# -002_plata_rele.net
KiCad netlist of a schematic drawn in Altium Designer
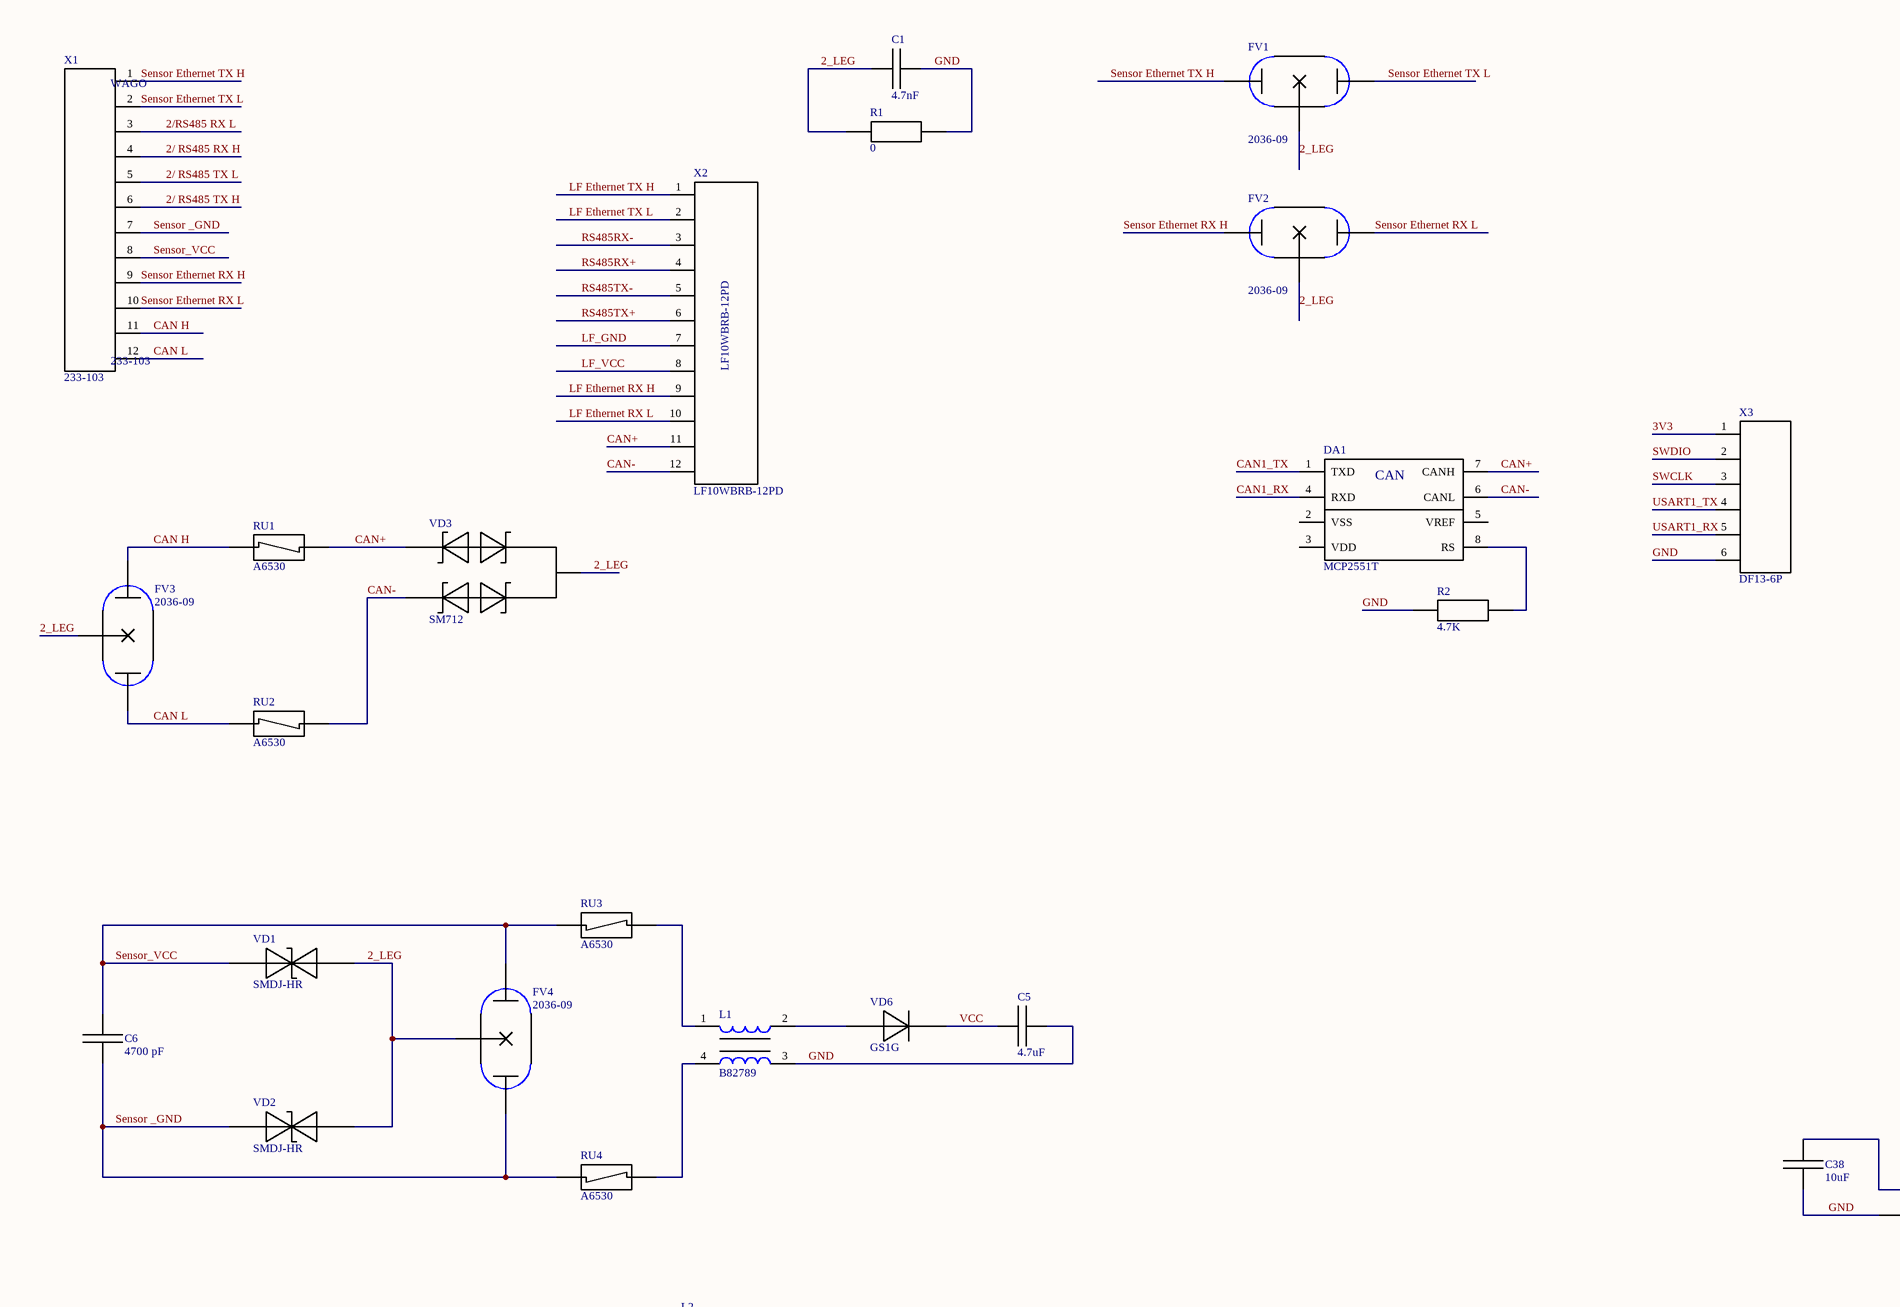
[diagram p0: КБ-002_plata_rele.SchDoc, top left]
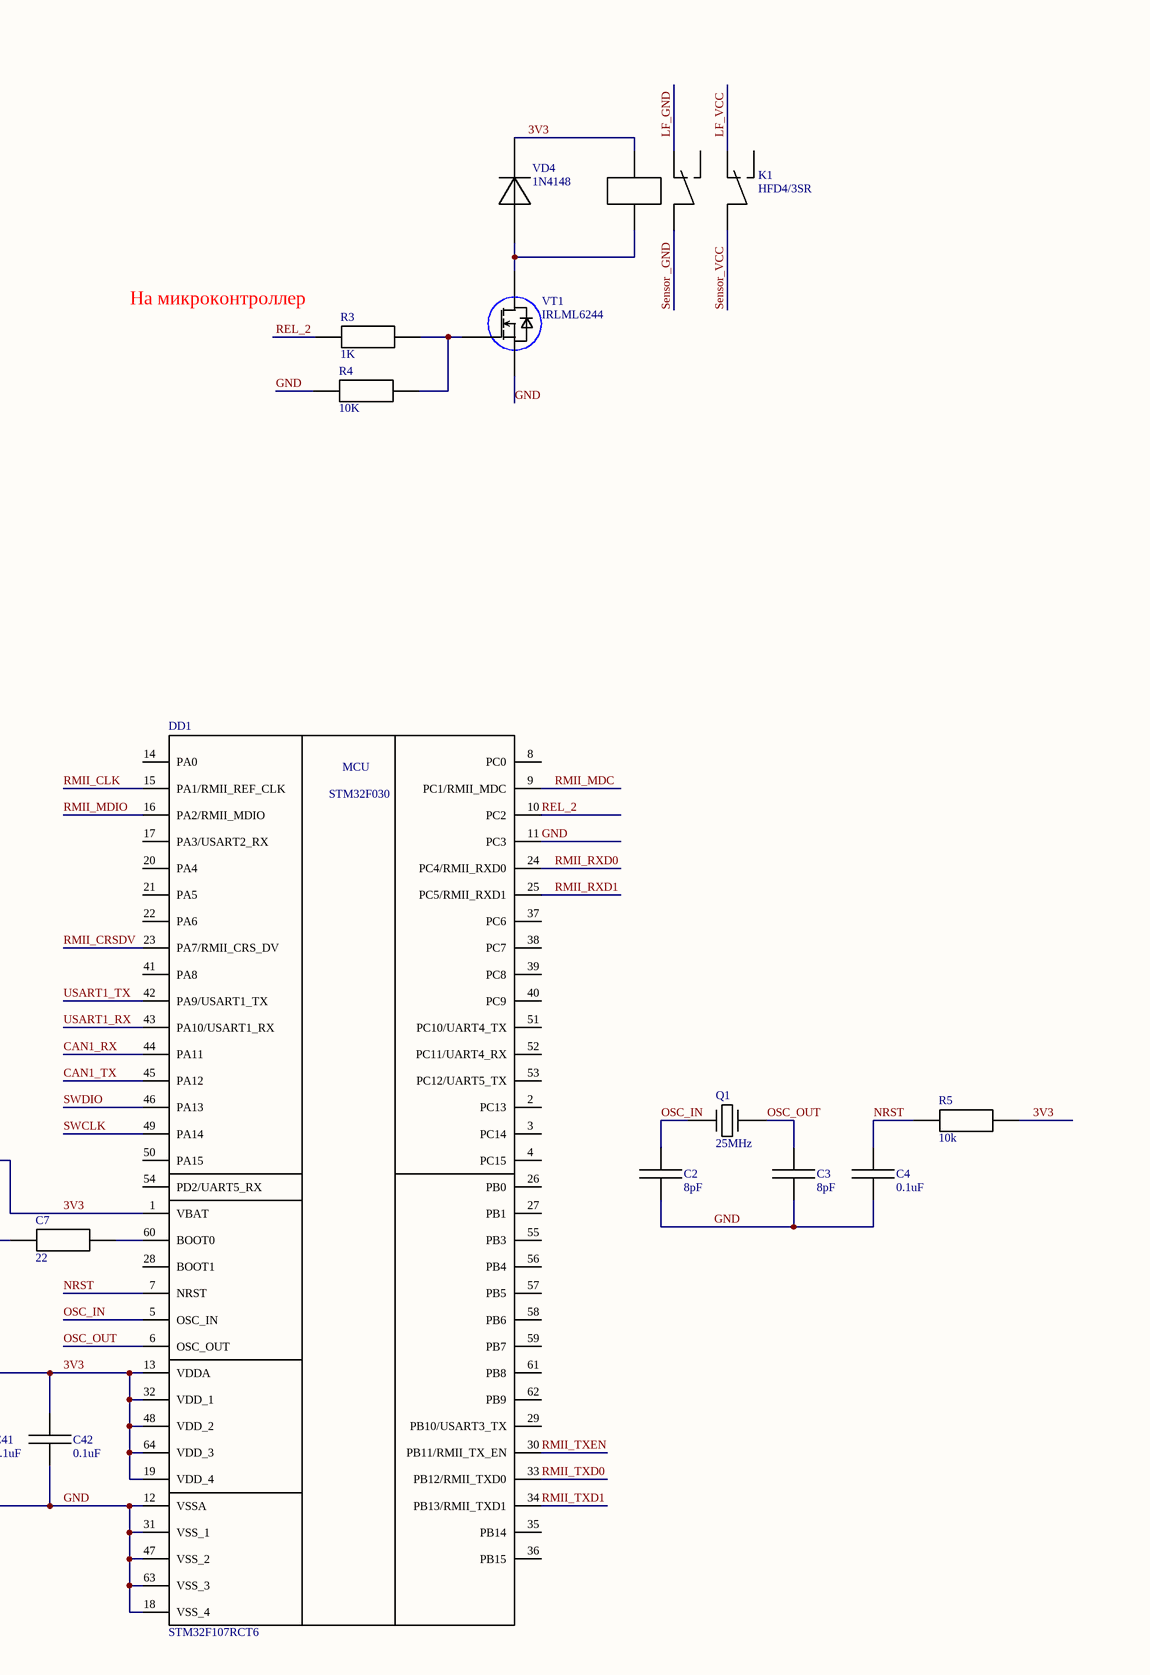
[diagram p1: КБ-002_plata_rele.SchDoc, top right]
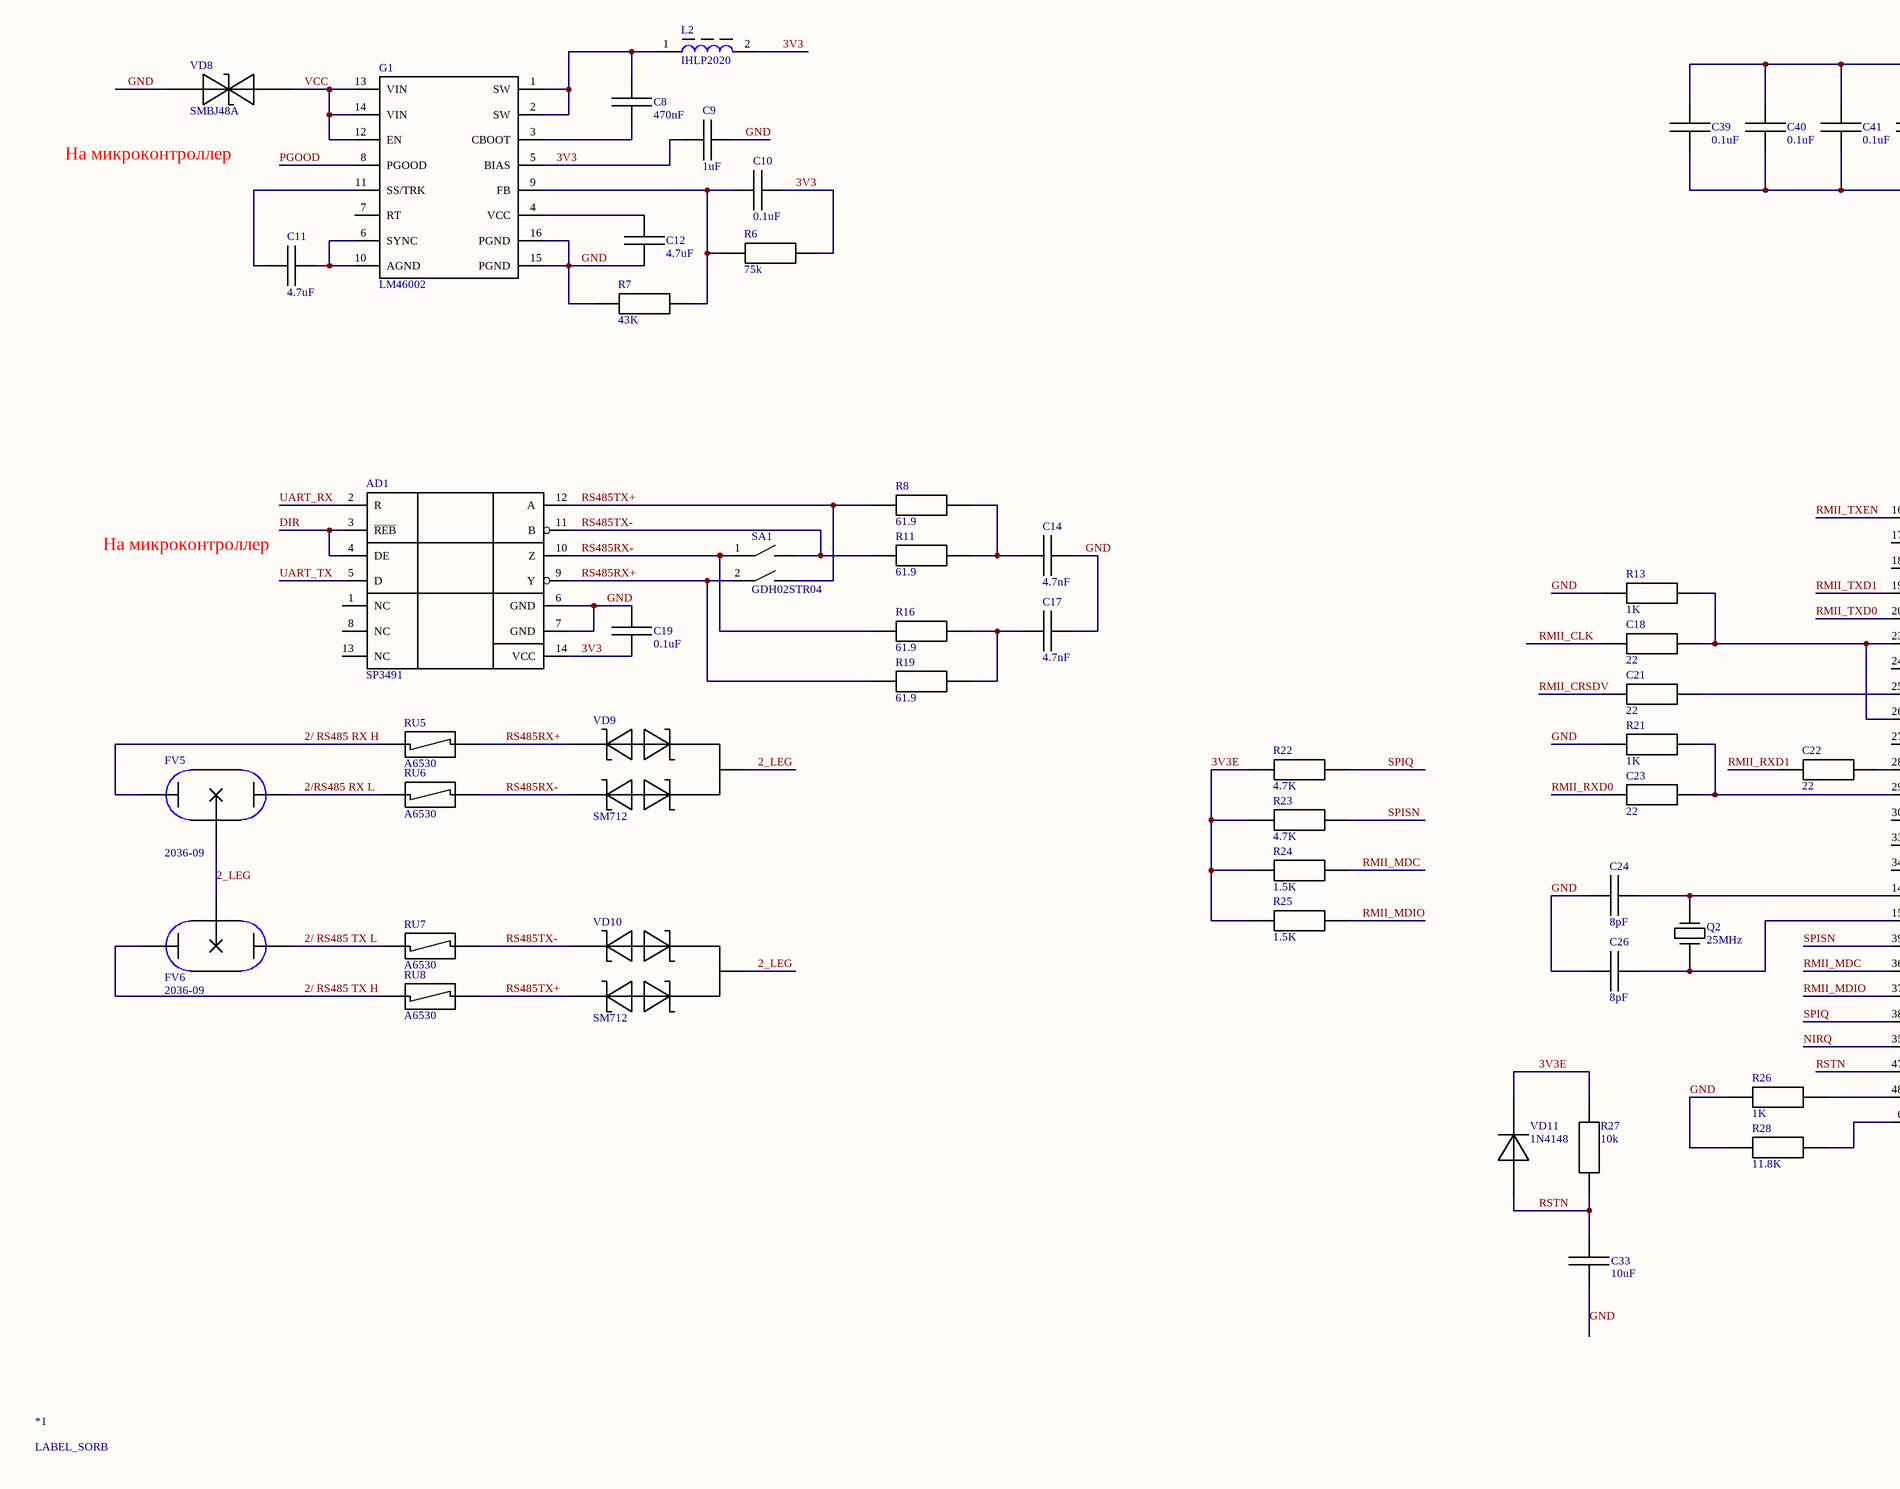
[diagram p2: КБ-002_plata_rele.SchDoc, bottom left]
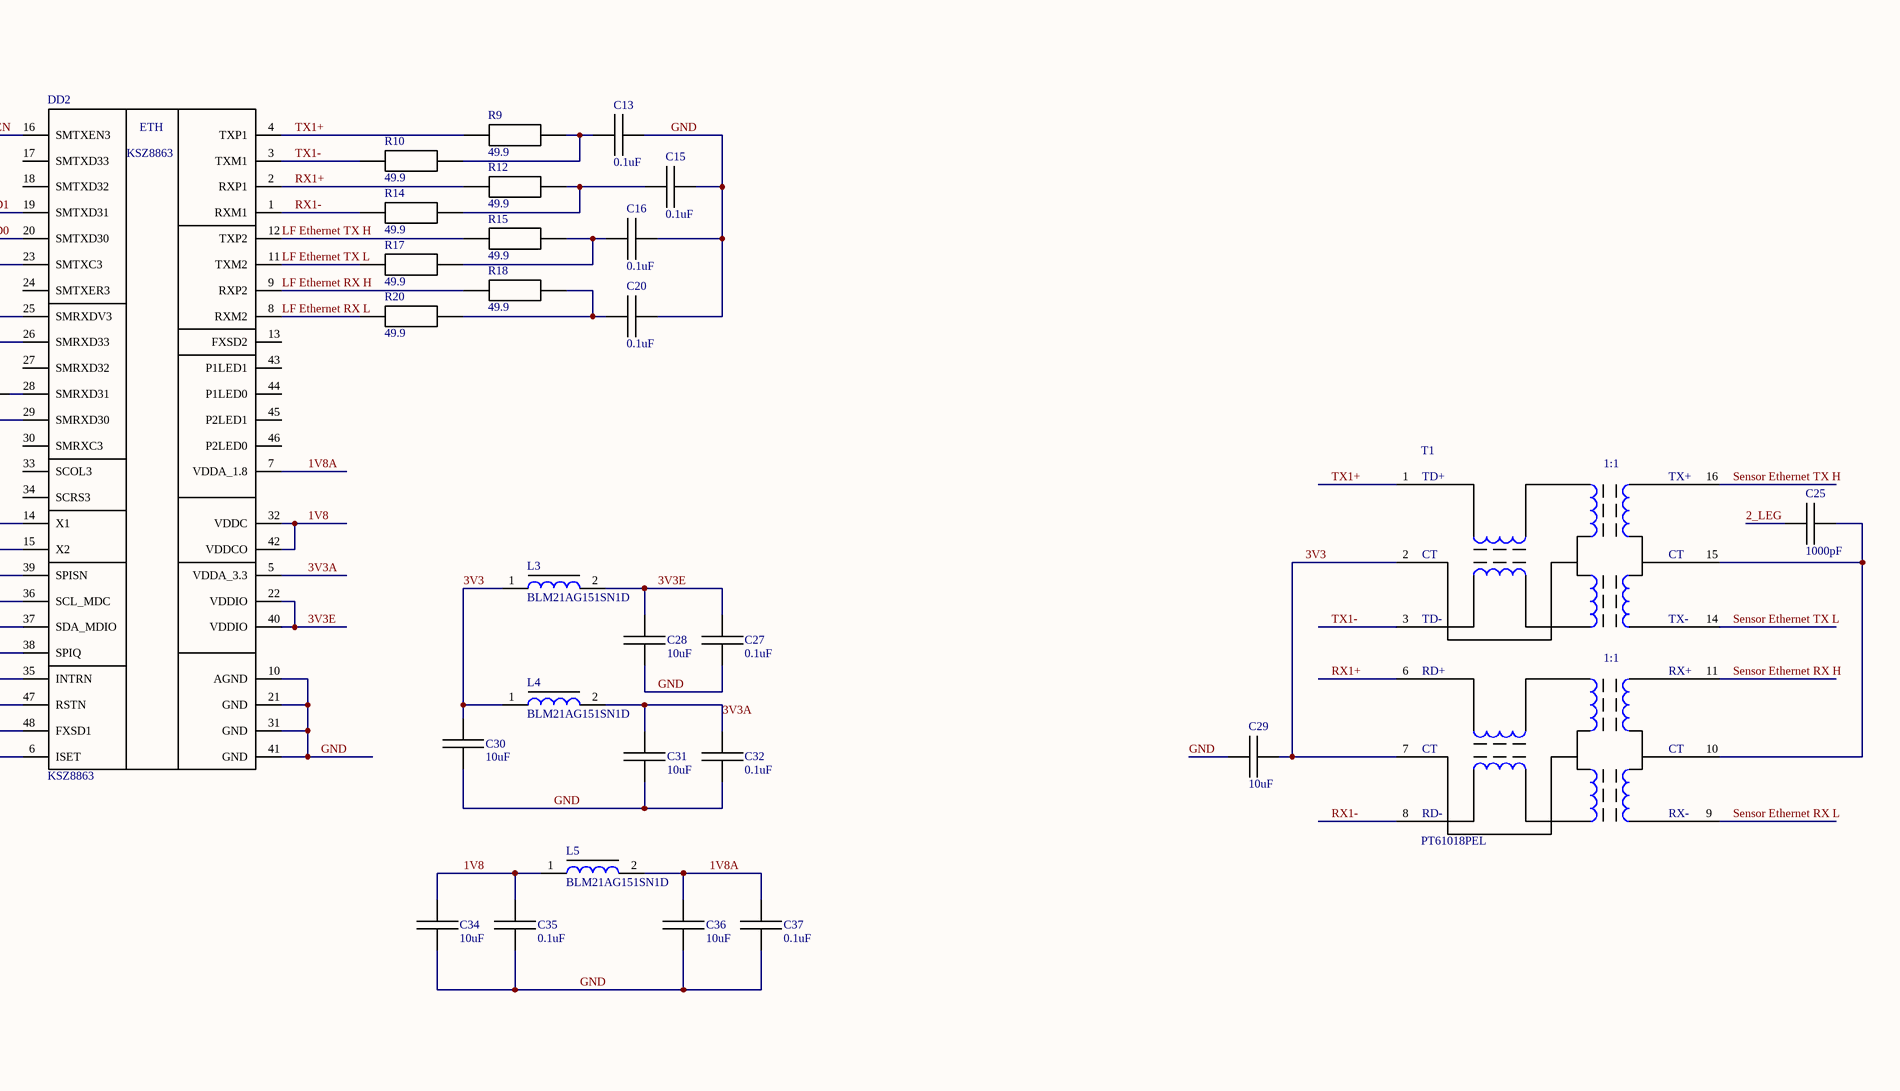
[diagram p3: КБ-002_plata_rele.SchDoc, bottom right]

(export (version "E")
  (design (tool "Eeschema 10.0.6"))
  (components
    (comp (ref "*1")
      (value "LABEL_SORB")
      (footprint "SorbGroup")
      (libsource (lib "pozarka") (part "LABEL_SORB"))
    )
    (comp (ref "AD1")
      (value "SP3491")
      (footprint "SOIC-14")
      (description "SP3491CN-L, Приемопередатчик RS485, 3В-3.465В, NSOIC-14")
      (libsource (lib "pozarka") (part "SP3491"))
    )
    (comp (ref "C1")
      (value "4.7nF")
      (footprint "CAP0402")
      (description "Кер.чип.конд. 0402 X5R 4.7нФ 16В 10%, GRM155R61C472KA01D")
      (libsource (lib "pozarka") (part "CAP0402 4.7nF"))
    )
    (comp (ref "C2")
      (value "8pF")
      (footprint "CAP0402")
      (description "Кер.чип.конд. 0402 C0G 8пФ 50В, GRM1555C1H8R0CA01D")
      (libsource (lib "pozarka") (part "CAP0402 8pF"))
    )
    (comp (ref "C3")
      (value "8pF")
      (footprint "CAP0402")
      (description "Кер.чип.конд. 0402 C0G 8пФ 50В, GRM1555C1H8R0CA01D")
      (libsource (lib "pozarka") (part "CAP0402 8pF"))
    )
    (comp (ref "C4")
      (value "0.1uF")
      (footprint "CAP0402")
      (description "Кер.ЧИП конд. 0.1мкФ X7R 10%, 0402, 16В, GRM155R71C104K")
      (libsource (lib "pozarka") (part "CAP0402 0.1uF"))
    )
    (comp (ref "C5")
      (value "4.7uF")
      (footprint "CAP0402")
      (description "Кер.чип.конд. 0402 X5R 4.7мкФ 4В 20%, GRM155R60G475ME87D")
      (libsource (lib "pozarka") (part "CAP0402 4,7uF"))
    )
    (comp (ref "C6")
      (value "4700 pF")
      (footprint "CAP1812")
      (description "4700пф X7R 2000в 10% (1812) Чип керам,конденсатор MA1812XR472K202ERG (FV43X472K202EFG")
      (libsource (lib "pozarka") (part "CAP1812 4700pF"))
    )
    (comp (ref "C7")
      (value "22")
      (footprint "RES0402")
      (description "0.062Вт 0402 22 Ом, 1%, Чип резистор (SMD)")
      (libsource (lib "pozarka") (part "RES0402 22"))
    )
    (comp (ref "C8")
      (value "470nF")
      (footprint "CAP0402")
      (description "Кер.чип.конд. 0402 X5R 470нФ 10В 10% , GRM155R61A474KE15D")
      (libsource (lib "pozarka") (part "CAP0402 470nF"))
    )
    (comp (ref "C9")
      (value "1uF")
      (footprint "CAP0402")
      (description "Кер.ЧИП конд. 1мкФ X5R 10%, 0402, 10В, GRM155R61A105K")
      (libsource (lib "pozarka") (part "CAP0402 1uF"))
    )
    (comp (ref "C10")
      (value "0.1uF")
      (footprint "CAP0402")
      (description "Кер.ЧИП конд. 0.1мкФ X7R 10%, 0402, 16В, GRM155R71C104K")
      (libsource (lib "pozarka") (part "CAP0402 0.1uF"))
    )
    (comp (ref "C11")
      (value "4.7uF")
      (footprint "CAP0402")
      (description "Кер.чип.конд. 0402 X5R 4.7мкФ 4В 20%, GRM155R60G475ME87D")
      (libsource (lib "pozarka") (part "CAP0402 4,7uF"))
    )
    (comp (ref "C12")
      (value "4.7uF")
      (footprint "CAP0402")
      (description "Кер.чип.конд. 0402 X5R 4.7мкФ 4В 20%, GRM155R60G475ME87D")
      (libsource (lib "pozarka") (part "CAP0402 4,7uF"))
    )
    (comp (ref "C13")
      (value "0.1uF")
      (footprint "CAP0402")
      (description "Кер.ЧИП конд. 0.1мкФ X7R 10%, 0402, 16В, GRM155R71C104K")
      (libsource (lib "pozarka") (part "CAP0402 0.1uF"))
    )
    (comp (ref "C14")
      (value "4.7nF")
      (footprint "CAP0402")
      (description "Кер.чип.конд. 0402 X5R 4.7нФ 16В 10%, GRM155R61C472KA01D")
      (libsource (lib "pozarka") (part "CAP0402 4.7nF"))
    )
    (comp (ref "C15")
      (value "0.1uF")
      (footprint "CAP0402")
      (description "Кер.ЧИП конд. 0.1мкФ X7R 10%, 0402, 16В, GRM155R71C104K")
      (libsource (lib "pozarka") (part "CAP0402 0.1uF"))
    )
    (comp (ref "C16")
      (value "0.1uF")
      (footprint "CAP0402")
      (description "Кер.ЧИП конд. 0.1мкФ X7R 10%, 0402, 16В, GRM155R71C104K")
      (libsource (lib "pozarka") (part "CAP0402 0.1uF"))
    )
    (comp (ref "C17")
      (value "4.7nF")
      (footprint "CAP0402")
      (description "Кер.чип.конд. 0402 X5R 4.7нФ 16В 10%, GRM155R61C472KA01D")
      (libsource (lib "pozarka") (part "CAP0402 4.7nF"))
    )
    (comp (ref "C18")
      (value "22")
      (footprint "RES0402")
      (description "0.062Вт 0402 22 Ом, 1%, Чип резистор (SMD)")
      (libsource (lib "pozarka") (part "RES0402 22"))
    )
    (comp (ref "C19")
      (value "0.1uF")
      (footprint "CAP0402")
      (description "Кер.ЧИП конд. 0.1мкФ X7R 10%, 0402, 16В, GRM155R71C104K")
      (libsource (lib "pozarka") (part "CAP0402 0.1uF"))
    )
    (comp (ref "C20")
      (value "0.1uF")
      (footprint "CAP0402")
      (description "Кер.ЧИП конд. 0.1мкФ X7R 10%, 0402, 16В, GRM155R71C104K")
      (libsource (lib "pozarka") (part "CAP0402 0.1uF"))
    )
    (comp (ref "C21")
      (value "22")
      (footprint "RES0402")
      (description "0.062Вт 0402 22 Ом, 1%, Чип резистор (SMD)")
      (libsource (lib "pozarka") (part "RES0402 22"))
    )
    (comp (ref "C22")
      (value "22")
      (footprint "RES0402")
      (description "0.062Вт 0402 22 Ом, 1%, Чип резистор (SMD)")
      (libsource (lib "pozarka") (part "RES0402 22"))
    )
    (comp (ref "C23")
      (value "22")
      (footprint "RES0402")
      (description "0.062Вт 0402 22 Ом, 1%, Чип резистор (SMD)")
      (libsource (lib "pozarka") (part "RES0402 22"))
    )
    (comp (ref "C24")
      (value "8pF")
      (footprint "CAP0402")
      (description "Кер.чип.конд. 0402 C0G 8пФ 50В, GRM1555C1H8R0CA01D")
      (libsource (lib "pozarka") (part "CAP0402 8pF"))
    )
    (comp (ref "C25")
      (value "1000pF")
      (footprint "CAP0402")
      (description "Кер.ЧИП конд. 1000пФ NP0 5%, 0402, 50В, GRM1555C1H102J")
      (libsource (lib "pozarka") (part "CAP0402 1000pF"))
    )
    (comp (ref "C26")
      (value "8pF")
      (footprint "CAP0402")
      (description "Кер.чип.конд. 0402 C0G 8пФ 50В, GRM1555C1H8R0CA01D")
      (libsource (lib "pozarka") (part "CAP0402 8pF"))
    )
    (comp (ref "C27")
      (value "0.1uF")
      (footprint "CAP0402")
      (description "Кер.ЧИП конд. 0.1мкФ X7R 10%, 0402, 16В, GRM155R71C104K")
      (libsource (lib "pozarka") (part "CAP0402 0.1uF"))
    )
    (comp (ref "C28")
      (value "10uF")
      (footprint "CAP0402")
      (description "Кер.чип.конд. 0402 X5R 10мкФ 2.5В 20%, GRM155R60E106ME16D")
      (libsource (lib "pozarka") (part "CAP0402 10uF"))
    )
    (comp (ref "C29")
      (value "10uF")
      (footprint "CAP0402")
      (description "Кер.чип.конд. 0402 X5R 10мкФ 2.5В 20%, GRM155R60E106ME16D")
      (libsource (lib "pozarka") (part "CAP0402 10uF"))
    )
    (comp (ref "C30")
      (value "10uF")
      (footprint "CAP0402")
      (description "Кер.чип.конд. 0402 X5R 10мкФ 2.5В 20%, GRM155R60E106ME16D")
      (libsource (lib "pozarka") (part "CAP0402 10uF"))
    )
    (comp (ref "C31")
      (value "10uF")
      (footprint "CAP0402")
      (description "Кер.чип.конд. 0402 X5R 10мкФ 2.5В 20%, GRM155R60E106ME16D")
      (libsource (lib "pozarka") (part "CAP0402 10uF"))
    )
    (comp (ref "C32")
      (value "0.1uF")
      (footprint "CAP0402")
      (description "Кер.ЧИП конд. 0.1мкФ X7R 10%, 0402, 16В, GRM155R71C104K")
      (libsource (lib "pozarka") (part "CAP0402 0.1uF"))
    )
    (comp (ref "C33")
      (value "10uF")
      (footprint "CAP0402")
      (description "Кер.чип.конд. 0402 X5R 10мкФ 2.5В 20%, GRM155R60E106ME16D")
      (libsource (lib "pozarka") (part "CAP0402 10uF"))
    )
    (comp (ref "C34")
      (value "10uF")
      (footprint "CAP0402")
      (description "Кер.чип.конд. 0402 X5R 10мкФ 2.5В 20%, GRM155R60E106ME16D")
      (libsource (lib "pozarka") (part "CAP0402 10uF"))
    )
    (comp (ref "C35")
      (value "0.1uF")
      (footprint "CAP0402")
      (description "Кер.ЧИП конд. 0.1мкФ X7R 10%, 0402, 16В, GRM155R71C104K")
      (libsource (lib "pozarka") (part "CAP0402 0.1uF"))
    )
    (comp (ref "C36")
      (value "10uF")
      (footprint "CAP0402")
      (description "Кер.чип.конд. 0402 X5R 10мкФ 2.5В 20%, GRM155R60E106ME16D")
      (libsource (lib "pozarka") (part "CAP0402 10uF"))
    )
    (comp (ref "C37")
      (value "0.1uF")
      (footprint "CAP0402")
      (description "Кер.ЧИП конд. 0.1мкФ X7R 10%, 0402, 16В, GRM155R71C104K")
      (libsource (lib "pozarka") (part "CAP0402 0.1uF"))
    )
    (comp (ref "C38")
      (value "10uF")
      (footprint "CAP0402")
      (description "Кер.чип.конд. 0402 X5R 10мкФ 2.5В 20%, GRM155R60E106ME16D")
      (libsource (lib "pozarka") (part "CAP0402 10uF"))
    )
    (comp (ref "C39")
      (value "0.1uF")
      (footprint "CAP0402")
      (description "Кер.ЧИП конд. 0.1мкФ X7R 10%, 0402, 16В, GRM155R71C104K")
      (libsource (lib "pozarka") (part "CAP0402 0.1uF"))
    )
    (comp (ref "C40")
      (value "0.1uF")
      (footprint "CAP0402")
      (description "Кер.ЧИП конд. 0.1мкФ X7R 10%, 0402, 16В, GRM155R71C104K")
      (libsource (lib "pozarka") (part "CAP0402 0.1uF"))
    )
    (comp (ref "C41")
      (value "0.1uF")
      (footprint "CAP0402")
      (description "Кер.ЧИП конд. 0.1мкФ X7R 10%, 0402, 16В, GRM155R71C104K")
      (libsource (lib "pozarka") (part "CAP0402 0.1uF"))
    )
    (comp (ref "C42")
      (value "0.1uF")
      (footprint "CAP0402")
      (description "Кер.ЧИП конд. 0.1мкФ X7R 10%, 0402, 16В, GRM155R71C104K")
      (libsource (lib "pozarka") (part "CAP0402 0.1uF"))
    )
    (comp (ref "DA1")
      (value "MCP2551T")
      (footprint "SO-8")
      (description "MCP2551T-I/SN, CAN приемопередатчик, быстрый [SO-8]")
      (libsource (lib "pozarka") (part "MCPT2551T"))
    )
    (comp (ref "DD1")
      (value "STM32F107RCT6")
      (footprint "TQFP64 10x10")
      (description "STM32F107RCT6, Микроконтроллер 32-Бит, Cortex-M3, 72МГц, 256КБ Flash [LQFP-64]")
      (libsource (lib "pozarka") (part "STM32F107"))
    )
    (comp (ref "DD2") (value "KSZ8863") (footprint "TQFP48-7x7") (libsource (lib "pozarka") (part "KSZ8863")))
    (comp (ref "FV1")
      (value "2036-09")
      (footprint "2036-09")
      (description "2036-09-SM-RPLF Газоразрядная трубка")
      (libsource (lib "pozarka") (part "2036-09"))
    )
    (comp (ref "FV2")
      (value "2036-09")
      (footprint "2036-09")
      (description "2036-09-SM-RPLF Газоразрядная трубка")
      (libsource (lib "pozarka") (part "2036-09"))
    )
    (comp (ref "FV3")
      (value "2036-09")
      (footprint "2036-09")
      (description "2036-09-SM-RPLF Газоразрядная трубка")
      (libsource (lib "pozarka") (part "2036-09"))
    )
    (comp (ref "FV4")
      (value "2036-09")
      (footprint "2036-09")
      (description "2036-09-SM-RPLF Газоразрядная трубка")
      (libsource (lib "pozarka") (part "2036-09"))
    )
    (comp (ref "FV5")
      (value "2036-09")
      (footprint "2036-09")
      (description "2036-09-SM-RPLF Газоразрядная трубка")
      (libsource (lib "pozarka") (part "2036-09"))
    )
    (comp (ref "FV6")
      (value "2036-09")
      (footprint "2036-09")
      (description "2036-09-SM-RPLF Газоразрядная трубка")
      (libsource (lib "pozarka") (part "2036-09"))
    )
    (comp (ref "G1") (value "LM46002") (footprint "HTSSOP-16") (libsource (lib "pozarka") (part "LM46002")))
    (comp (ref "K1")
      (value "HFD4/3SR")
      (footprint "HFD4/3")
      (description "HFD4/3SR (IM01GR), Реле 3VDC 2пер. 2A/250VAC")
      (libsource (lib "pozarka") (part "HFD4/3SR"))
    )
    (comp (ref "L1")
      (value "B82789")
      (footprint "SIMDAD 1812")
      (description "B82789C0104N002")
      (libsource (lib "pozarka") (part "B82789"))
    )
    (comp (ref "L2")
      (value "IHLP2020")
      (footprint "IHLP-2020CZ-51")
      (description "IHLP2020CZER100M11")
      (libsource (lib "pozarka") (part "IHLP2020CZER100M11"))
    )
    (comp (ref "L3")
      (value "BLM21AG151SN1D")
      (footprint "IND0805")
      (libsource (lib "pozarka") (part "BLM21AG151SN1D"))
    )
    (comp (ref "L4")
      (value "BLM21AG151SN1D")
      (footprint "IND0805")
      (libsource (lib "pozarka") (part "BLM21AG151SN1D"))
    )
    (comp (ref "L5")
      (value "BLM21AG151SN1D")
      (footprint "IND0805")
      (libsource (lib "pozarka") (part "BLM21AG151SN1D"))
    )
    (comp (ref "Q1")
      (value "25MHz")
      (footprint "3225 CRYSTAL")
      (description "NX3225SA-25MHZ, 25 МГц, 15/25ppm, 8пФ, -40...+85°C, SMD 3.2*2.5*0.55мм, Кварцевый резонатор")
      (libsource (lib "pozarka") (part "25MHz"))
    )
    (comp (ref "Q2")
      (value "25MHz")
      (footprint "3225 CRYSTAL")
      (description "NX3225SA-25MHZ, 25 МГц, 15/25ppm, 8пФ, -40...+85°C, SMD 3.2*2.5*0.55мм, Кварцевый резонатор")
      (libsource (lib "pozarka") (part "25MHz"))
    )
    (comp (ref "R1")
      (value "0")
      (footprint "RES0402")
      (description "0.062Вт 0402 0 Ом 5%, Чип резистор (SMD)")
      (libsource (lib "pozarka") (part "RES0402 0"))
    )
    (comp (ref "R2")
      (value "4.7K")
      (footprint "RES0402")
      (description "0.062Вт 0402 4.7 кОм, 5%, Чип резистор (SMD)")
      (libsource (lib "pozarka") (part "RES0402 4.7K"))
    )
    (comp (ref "R3")
      (value "1K")
      (footprint "RES0603")
      (description "0.063Вт 0603 1 кОм, 1%, Чип резистор (SMD)")
      (libsource (lib "pozarka") (part "RES0603 1K"))
    )
    (comp (ref "R4")
      (value "10K")
      (footprint "RES0603")
      (description "0.063Вт 0603 10 кОм, 1%, Чип резистор (SMD)")
      (libsource (lib "pozarka") (part "RES0603 10K"))
    )
    (comp (ref "R5")
      (value "10k")
      (footprint "RES0402")
      (description "0.062Вт 0402 10 кОм, 1%, Чип резистор (SMD)")
      (libsource (lib "pozarka") (part "RES0402 10k"))
    )
    (comp (ref "R6")
      (value "75k")
      (footprint "RES0402")
      (description "0.062Вт 0402 75 кОм, 1%, Чип резистор (SMD)")
      (libsource (lib "pozarka") (part "RES0402 75k"))
    )
    (comp (ref "R7")
      (value "43K")
      (footprint "RES0402")
      (description "0.062Вт 0402 43 кОм, 1%, Чип резистор (SMD)")
      (libsource (lib "pozarka") (part "RES0402 43K"))
    )
    (comp (ref "R8")
      (value "61.9")
      (footprint "RES0402")
      (description "0.062Вт 0402 62 Ом, 1%, Чип резистор (SMD)")
      (libsource (lib "pozarka") (part "RES0402 61.9"))
    )
    (comp (ref "R9")
      (value "49.9")
      (footprint "RES0402")
      (description "49,9 Ом 1% 0402 FCF02FV-49R9 чип-резистор PDC")
      (libsource (lib "pozarka") (part "RES0402 49.9"))
    )
    (comp (ref "R10")
      (value "49.9")
      (footprint "RES0402")
      (description "49,9 Ом 1% 0402 FCF02FV-49R9 чип-резистор PDC")
      (libsource (lib "pozarka") (part "RES0402 49.9"))
    )
    (comp (ref "R11")
      (value "61.9")
      (footprint "RES0402")
      (description "0.062Вт 0402 62 Ом, 1%, Чип резистор (SMD)")
      (libsource (lib "pozarka") (part "RES0402 61.9"))
    )
    (comp (ref "R12")
      (value "49.9")
      (footprint "RES0402")
      (description "49,9 Ом 1% 0402 FCF02FV-49R9 чип-резистор PDC")
      (libsource (lib "pozarka") (part "RES0402 49.9"))
    )
    (comp (ref "R13")
      (value "1K")
      (footprint "RES0402")
      (description "0.062Вт 0402 1 кОм, 1%, Чип резистор (SMD)")
      (libsource (lib "pozarka") (part "RES0402 1K"))
    )
    (comp (ref "R14")
      (value "49.9")
      (footprint "RES0402")
      (description "49,9 Ом 1% 0402 FCF02FV-49R9 чип-резистор PDC")
      (libsource (lib "pozarka") (part "RES0402 49.9"))
    )
    (comp (ref "R15")
      (value "49.9")
      (footprint "RES0402")
      (description "49,9 Ом 1% 0402 FCF02FV-49R9 чип-резистор PDC")
      (libsource (lib "pozarka") (part "RES0402 49.9"))
    )
    (comp (ref "R16")
      (value "61.9")
      (footprint "RES0402")
      (description "0.062Вт 0402 62 Ом, 1%, Чип резистор (SMD)")
      (libsource (lib "pozarka") (part "RES0402 61.9"))
    )
    (comp (ref "R17")
      (value "49.9")
      (footprint "RES0402")
      (description "49,9 Ом 1% 0402 FCF02FV-49R9 чип-резистор PDC")
      (libsource (lib "pozarka") (part "RES0402 49.9"))
    )
    (comp (ref "R18")
      (value "49.9")
      (footprint "RES0402")
      (description "49,9 Ом 1% 0402 FCF02FV-49R9 чип-резистор PDC")
      (libsource (lib "pozarka") (part "RES0402 49.9"))
    )
    (comp (ref "R19")
      (value "61.9")
      (footprint "RES0402")
      (description "0.062Вт 0402 62 Ом, 1%, Чип резистор (SMD)")
      (libsource (lib "pozarka") (part "RES0402 61.9"))
    )
    (comp (ref "R20")
      (value "49.9")
      (footprint "RES0402")
      (description "49,9 Ом 1% 0402 FCF02FV-49R9 чип-резистор PDC")
      (libsource (lib "pozarka") (part "RES0402 49.9"))
    )
    (comp (ref "R21")
      (value "1K")
      (footprint "RES0402")
      (description "0.062Вт 0402 1 кОм, 1%, Чип резистор (SMD)")
      (libsource (lib "pozarka") (part "RES0402 1K"))
    )
    (comp (ref "R22")
      (value "4.7K")
      (footprint "RES0402")
      (description "0.062Вт 0402 4.7 кОм, 5%, Чип резистор (SMD)")
      (libsource (lib "pozarka") (part "RES0402 4.7K"))
    )
    (comp (ref "R23")
      (value "4.7K")
      (footprint "RES0402")
      (description "0.062Вт 0402 4.7 кОм, 5%, Чип резистор (SMD)")
      (libsource (lib "pozarka") (part "RES0402 4.7K"))
    )
    (comp (ref "R24")
      (value "1.5K")
      (footprint "RES0402")
      (description "0.062Вт 0402 1.5 кОм, 1%, Чип резистор (SMD)")
      (libsource (lib "pozarka") (part "RES0402 1.5K"))
    )
    (comp (ref "R25")
      (value "1.5K")
      (footprint "RES0402")
      (description "0.062Вт 0402 1.5 кОм, 1%, Чип резистор (SMD)")
      (libsource (lib "pozarka") (part "RES0402 1.5K"))
    )
    (comp (ref "R26")
      (value "1K")
      (footprint "RES0402")
      (description "0.062Вт 0402 1 кОм, 1%, Чип резистор (SMD)")
      (libsource (lib "pozarka") (part "RES0402 1K"))
    )
    (comp (ref "R27")
      (value "10k")
      (footprint "RES0402")
      (description "0.062Вт 0402 10 кОм, 1%, Чип резистор (SMD)")
      (libsource (lib "pozarka") (part "RES0402 10k"))
    )
    (comp (ref "R28")
      (value "11.8K")
      (footprint "RES0603")
      (description "11,8 кОм 0603 1% RI0603L1182FT чип резистор Hottech")
      (libsource (lib "pozarka") (part "RES0603 11.8K"))
    )
    (comp (ref "RU1")
      (value "A6530")
      (footprint "TBU-CA")
      (description "TBU-CA065-300-WH, Защитная ИС")
      (libsource (lib "pozarka") (part "TBU-CA"))
    )
    (comp (ref "RU2")
      (value "A6530")
      (footprint "TBU-CA")
      (description "TBU-CA065-300-WH, Защитная ИС")
      (libsource (lib "pozarka") (part "TBU-CA"))
    )
    (comp (ref "RU3")
      (value "A6530")
      (footprint "TBU-CA")
      (description "TBU-CA065-300-WH, Защитная ИС")
      (libsource (lib "pozarka") (part "TBU-CA"))
    )
    (comp (ref "RU4")
      (value "A6530")
      (footprint "TBU-CA")
      (description "TBU-CA065-300-WH, Защитная ИС")
      (libsource (lib "pozarka") (part "TBU-CA"))
    )
    (comp (ref "RU5")
      (value "A6530")
      (footprint "TBU-CA")
      (description "TBU-CA065-300-WH, Защитная ИС")
      (libsource (lib "pozarka") (part "TBU-CA"))
    )
    (comp (ref "RU6")
      (value "A6530")
      (footprint "TBU-CA")
      (description "TBU-CA065-300-WH, Защитная ИС")
      (libsource (lib "pozarka") (part "TBU-CA"))
    )
    (comp (ref "RU7")
      (value "A6530")
      (footprint "TBU-CA")
      (description "TBU-CA065-300-WH, Защитная ИС")
      (libsource (lib "pozarka") (part "TBU-CA"))
    )
    (comp (ref "RU8")
      (value "A6530")
      (footprint "TBU-CA")
      (description "TBU-CA065-300-WH, Защитная ИС")
      (libsource (lib "pozarka") (part "TBU-CA"))
    )
    (comp (ref "SA1")
      (value "GDH02STR04")
      (footprint "Switch DIP2")
      (description "GDH02STR04, Switch DIP OFF ON SPST 2 Recessed Rocker 0.025A 24VDC Gull Wing 1.27mm SMD T/R")
      (libsource (lib "pozarka") (part "GDH02STR04"))
    )
    (comp (ref "T1")
      (value "PT61018PEL")
      (footprint "PT61018PEL")
      (libsource (lib "pozarka") (part "PT61018PEL"))
    )
    (comp (ref "VD1")
      (value "SMDJ-HR")
      (footprint "DO-214AB")
      (description "5.0SMDJ45A, TVS Diode Single Uni-Dir 45V 5KW 2-Pin SMC T/R")
      (libsource (lib "pozarka") (part "SMDJ"))
    )
    (comp (ref "VD2")
      (value "SMDJ-HR")
      (footprint "DO-214AB")
      (description "5.0SMDJ45A, TVS Diode Single Uni-Dir 45V 5KW 2-Pin SMC T/R")
      (libsource (lib "pozarka") (part "SMDJ"))
    )
    (comp (ref "VD3")
      (value "SM712")
      (footprint "SOT-23")
      (description "SM712.TCT, Диод защитный для устройсв стандарта RS-485, 400Вт, 12В, [SOT-23]")
      (libsource (lib "pozarka") (part "SM712"))
    )
    (comp (ref "VD4")
      (value "1N4148")
      (footprint "SOD-123")
      (description "1N4148W, Диод 150мА 100В [SOD-123]")
      (libsource (lib "pozarka") (part "1N4148"))
    )
    (comp (ref "VD6")
      (value "GS1G")
      (footprint "DO-214AC")
      (description "GS1G, Диод 1А 400В [DO-214AC / SMA]")
      (libsource (lib "pozarka") (part "GS1G"))
    )
    (comp (ref "VD8")
      (value "SMBJ48A")
      (footprint "DO-214AA")
      (description "SMBJ48A-TR, Защитный диод, 600Вт, 48В, [SMB / DO-214AA]")
      (libsource (lib "pozarka") (part "SMBJ48A"))
    )
    (comp (ref "VD9")
      (value "SM712")
      (footprint "SOT-23")
      (description "SM712.TCT, Диод защитный для устройсв стандарта RS-485, 400Вт, 12В, [SOT-23]")
      (libsource (lib "pozarka") (part "SM712"))
    )
    (comp (ref "VD10")
      (value "SM712")
      (footprint "SOT-23")
      (description "SM712.TCT, Диод защитный для устройсв стандарта RS-485, 400Вт, 12В, [SOT-23]")
      (libsource (lib "pozarka") (part "SM712"))
    )
    (comp (ref "VD11")
      (value "1N4148")
      (footprint "SOD-123")
      (description "1N4148W, Диод 150мА 100В [SOD-123]")
      (libsource (lib "pozarka") (part "1N4148"))
    )
    (comp (ref "VT1")
      (value "IRLML6244")
      (footprint "SOT-23")
      (description "IRLML6244TRPBF, Транзистор, N-канал 20В 6.3А [Micro3 / SOT-23]")
      (libsource (lib "pozarka") (part "IRLML6244"))
    )
    (comp (ref "X1")
      (value "233-103")
      (footprint "WAGO 233-103")
      (libsource (lib "pozarka") (part "WAGO 233-103"))
    )
    (comp (ref "X2")
      (value "LF10WBRB-12PD")
      (footprint "LF10WBRB-12PD")
      (description "LF10WBRB-12S, LF Series Miniature Panel Mount Connector, 12 contacts Socket")
      (libsource (lib "pozarka") (part "LF10WBRB-12PD"))
    )
    (comp (ref "X3")
      (value "DF13-6P")
      (footprint "DF13-6P")
      (description "DF13-6P-1.25DSA")
      (libsource (lib "pozarka") (part "DF13-6P"))
    )
  )
  (nets
    (net (code "1") (name "/1V8") (class "Default")
      (node (ref "C34") (pin "2") (pinfunction "2_2") (pintype "passive"))
      (node (ref "C35") (pin "2") (pinfunction "2_2") (pintype "passive"))
      (node (ref "DD2") (pin "32") (pinfunction "VDDC_32") (pintype "passive"))
      (node (ref "DD2") (pin "42") (pinfunction "VDDCO_42") (pintype "passive"))
      (node (ref "L5") (pin "1") (pinfunction "1_1") (pintype "passive"))
    )
    (net (code "2") (name "/1V8A") (class "Default")
      (node (ref "C36") (pin "2") (pinfunction "2_2") (pintype "passive"))
      (node (ref "C37") (pin "2") (pinfunction "2_2") (pintype "passive"))
      (node (ref "DD2") (pin "7") (pinfunction "VDDA_1.8_7") (pintype "passive"))
      (node (ref "L5") (pin "2") (pinfunction "2_2") (pintype "passive"))
    )
    (net (code "3") (name "/2_LEG") (class "Default")
      (node (ref "C1") (pin "1") (pinfunction "1_1") (pintype "passive"))
      (node (ref "C25") (pin "1") (pinfunction "1_1") (pintype "passive"))
      (node (ref "FV1") (pin "2") (pinfunction "2_2") (pintype "passive"))
      (node (ref "FV2") (pin "2") (pinfunction "2_2") (pintype "passive"))
      (node (ref "FV3") (pin "2") (pinfunction "2_2") (pintype "passive"))
      (node (ref "FV4") (pin "2") (pinfunction "2_2") (pintype "passive"))
      (node (ref "FV5") (pin "2") (pinfunction "2_2") (pintype "passive"))
      (node (ref "FV6") (pin "2") (pinfunction "2_2") (pintype "passive"))
      (node (ref "R1") (pin "1") (pinfunction "1_1") (pintype "passive"))
      (node (ref "VD1") (pin "2") (pinfunction "2_2") (pintype "passive"))
      (node (ref "VD10") (pin "3") (pinfunction "3_3") (pintype "passive"))
      (node (ref "VD2") (pin "2") (pinfunction "2_2") (pintype "passive"))
      (node (ref "VD3") (pin "3") (pinfunction "3_3") (pintype "passive"))
      (node (ref "VD9") (pin "3") (pinfunction "3_3") (pintype "passive"))
    )
    (net (code "4") (name "/2{slash} RS485 RX H") (class "Default")
      (node (ref "FV5") (pin "1") (pinfunction "1_1") (pintype "passive"))
      (node (ref "RU5") (pin "1") (pinfunction "1_1") (pintype "passive"))
      (node (ref "X1") (pin "4") (pinfunction "4_4") (pintype "passive"))
    )
    (net (code "5") (name "/2{slash} RS485 TX H") (class "Default")
      (node (ref "FV6") (pin "3") (pinfunction "3_3") (pintype "passive"))
      (node (ref "RU8") (pin "1") (pinfunction "1_1") (pintype "passive"))
      (node (ref "X1") (pin "6") (pinfunction "6_6") (pintype "passive"))
    )
    (net (code "6") (name "/2{slash} RS485 TX L") (class "Default")
      (node (ref "FV6") (pin "1") (pinfunction "1_1") (pintype "passive"))
      (node (ref "RU7") (pin "1") (pinfunction "1_1") (pintype "passive"))
      (node (ref "X1") (pin "5") (pinfunction "5_5") (pintype "passive"))
    )
    (net (code "7") (name "/2{slash}RS485 RX L") (class "Default")
      (node (ref "FV5") (pin "3") (pinfunction "3_3") (pintype "passive"))
      (node (ref "RU6") (pin "1") (pinfunction "1_1") (pintype "passive"))
      (node (ref "X1") (pin "3") (pinfunction "3_3") (pintype "passive"))
    )
    (net (code "8") (name "/3V3") (class "Default")
      (node (ref "AD1") (pin "14") (pinfunction "VCC_14") (pintype "passive"))
      (node (ref "C10") (pin "2") (pinfunction "2_2") (pintype "passive"))
      (node (ref "C19") (pin "1") (pinfunction "1_1") (pintype "passive"))
      (node (ref "C29") (pin "2") (pinfunction "2_2") (pintype "passive"))
      (node (ref "C30") (pin "2") (pinfunction "2_2") (pintype "passive"))
      (node (ref "C38") (pin "2") (pinfunction "2_2") (pintype "passive"))
      (node (ref "C39") (pin "2") (pinfunction "2_2") (pintype "passive"))
      (node (ref "C40") (pin "2") (pinfunction "2_2") (pintype "passive"))
      (node (ref "C41") (pin "2") (pinfunction "2_2") (pintype "passive"))
      (node (ref "C42") (pin "2") (pinfunction "2_2") (pintype "passive"))
      (node (ref "C9") (pin "1") (pinfunction "1_1") (pintype "passive"))
      (node (ref "DD1") (pin "1") (pinfunction "VBAT_1") (pintype "passive"))
      (node (ref "DD1") (pin "13") (pinfunction "VDDA_13") (pintype "passive"))
      (node (ref "DD1") (pin "19") (pinfunction "VDD_4_19") (pintype "passive"))
      (node (ref "DD1") (pin "32") (pinfunction "VDD_1_32") (pintype "passive"))
      (node (ref "DD1") (pin "48") (pinfunction "VDD_2_48") (pintype "passive"))
      (node (ref "DD1") (pin "64") (pinfunction "VDD_3_64") (pintype "passive"))
      (node (ref "G1") (pin "5") (pinfunction "BIAS_5") (pintype "passive"))
      (node (ref "K1") (pin "1") (pinfunction "1_1") (pintype "passive"))
      (node (ref "L2") (pin "2") (pinfunction "2_2") (pintype "passive"))
      (node (ref "L3") (pin "1") (pinfunction "1_1") (pintype "passive"))
      (node (ref "L4") (pin "1") (pinfunction "1_1") (pintype "passive"))
      (node (ref "R5") (pin "2") (pinfunction "2_2") (pintype "passive"))
      (node (ref "R6") (pin "2") (pinfunction "2_2") (pintype "passive"))
      (node (ref "T1") (pin "2") (pinfunction "2_2") (pintype "passive"))
      (node (ref "T1") (pin "7") (pinfunction "7_7") (pintype "passive"))
      (node (ref "VD4") (pin "2") (pinfunction "2_2") (pintype "passive"))
      (node (ref "X3") (pin "1") (pinfunction "1_1") (pintype "passive"))
    )
    (net (code "9") (name "/3V3A") (class "Default")
      (node (ref "C31") (pin "2") (pinfunction "2_2") (pintype "passive"))
      (node (ref "C32") (pin "1") (pinfunction "1_1") (pintype "passive"))
      (node (ref "DD2") (pin "5") (pinfunction "VDDA_3.3_5") (pintype "passive"))
      (node (ref "L4") (pin "2") (pinfunction "2_2") (pintype "passive"))
    )
    (net (code "10") (name "/3V3E") (class "Default")
      (node (ref "C27") (pin "2") (pinfunction "2_2") (pintype "passive"))
      (node (ref "C28") (pin "2") (pinfunction "2_2") (pintype "passive"))
      (node (ref "DD2") (pin "22") (pinfunction "VDDIO_22") (pintype "passive"))
      (node (ref "DD2") (pin "40") (pinfunction "VDDIO_40") (pintype "passive"))
      (node (ref "L3") (pin "2") (pinfunction "2_2") (pintype "passive"))
      (node (ref "R22") (pin "1") (pinfunction "1_1") (pintype "passive"))
      (node (ref "R23") (pin "1") (pinfunction "1_1") (pintype "passive"))
      (node (ref "R24") (pin "1") (pinfunction "1_1") (pintype "passive"))
      (node (ref "R25") (pin "1") (pinfunction "1_1") (pintype "passive"))
      (node (ref "R27") (pin "2") (pinfunction "2_2") (pintype "passive"))
      (node (ref "VD11") (pin "2") (pinfunction "2_2") (pintype "passive"))
    )
    (net (code "11") (name "/CAN H") (class "Default")
      (node (ref "FV3") (pin "1") (pinfunction "1_1") (pintype "passive"))
      (node (ref "RU1") (pin "2") (pinfunction "2_2") (pintype "passive"))
      (node (ref "X1") (pin "11") (pinfunction "11_11") (pintype "passive"))
    )
    (net (code "12") (name "/CAN L") (class "Default")
      (node (ref "FV3") (pin "3") (pinfunction "3_3") (pintype "passive"))
      (node (ref "RU2") (pin "2") (pinfunction "2_2") (pintype "passive"))
      (node (ref "X1") (pin "12") (pinfunction "12_12") (pintype "passive"))
    )
    (net (code "13") (name "/CAN+") (class "Default")
      (node (ref "DA1") (pin "7") (pinfunction "CANH_7") (pintype "passive"))
      (node (ref "RU1") (pin "1") (pinfunction "1_1") (pintype "passive"))
      (node (ref "VD3") (pin "2") (pinfunction "2_2") (pintype "passive"))
      (node (ref "X2") (pin "11") (pinfunction "11_11") (pintype "passive"))
    )
    (net (code "14") (name "/CAN-") (class "Default")
      (node (ref "DA1") (pin "6") (pinfunction "CANL_6") (pintype "passive"))
      (node (ref "RU2") (pin "1") (pinfunction "1_1") (pintype "passive"))
      (node (ref "VD3") (pin "1") (pinfunction "1_1") (pintype "passive"))
      (node (ref "X2") (pin "12") (pinfunction "12_12") (pintype "passive"))
    )
    (net (code "15") (name "/CAN1_RX") (class "Default")
      (node (ref "DA1") (pin "4") (pinfunction "RXD_4") (pintype "passive"))
      (node (ref "DD1") (pin "44") (pinfunction "PA11_44") (pintype "passive"))
    )
    (net (code "16") (name "/CAN1_TX") (class "Default")
      (node (ref "DA1") (pin "1") (pinfunction "TXD_1") (pintype "passive"))
      (node (ref "DD1") (pin "45") (pinfunction "PA12_45") (pintype "passive"))
    )
    (net (code "17") (name "/DIR") (class "Default")
      (node (ref "AD1") (pin "3") (pinfunction "~{REB}_3") (pintype "passive"))
      (node (ref "AD1") (pin "4") (pinfunction "DE_4") (pintype "passive"))
    )
    (net (code "18") (name "/GND") (class "Default")
      (node (ref "AD1") (pin "6") (pinfunction "GND_6") (pintype "passive"))
      (node (ref "AD1") (pin "7") (pinfunction "GND_7") (pintype "passive"))
      (node (ref "C1") (pin "2") (pinfunction "2_2") (pintype "passive"))
      (node (ref "C12") (pin "1") (pinfunction "1_1") (pintype "passive"))
      (node (ref "C13") (pin "1") (pinfunction "1_1") (pintype "passive"))
      (node (ref "C14") (pin "2") (pinfunction "2_2") (pintype "passive"))
      (node (ref "C15") (pin "1") (pinfunction "1_1") (pintype "passive"))
      (node (ref "C16") (pin "2") (pinfunction "2_2") (pintype "passive"))
      (node (ref "C17") (pin "2") (pinfunction "2_2") (pintype "passive"))
      (node (ref "C19") (pin "2") (pinfunction "2_2") (pintype "passive"))
      (node (ref "C2") (pin "1") (pinfunction "1_1") (pintype "passive"))
      (node (ref "C20") (pin "2") (pinfunction "2_2") (pintype "passive"))
      (node (ref "C24") (pin "1") (pinfunction "1_1") (pintype "passive"))
      (node (ref "C26") (pin "1") (pinfunction "1_1") (pintype "passive"))
      (node (ref "C27") (pin "1") (pinfunction "1_1") (pintype "passive"))
      (node (ref "C28") (pin "1") (pinfunction "1_1") (pintype "passive"))
      (node (ref "C29") (pin "1") (pinfunction "1_1") (pintype "passive"))
      (node (ref "C3") (pin "1") (pinfunction "1_1") (pintype "passive"))
      (node (ref "C30") (pin "1") (pinfunction "1_1") (pintype "passive"))
      (node (ref "C31") (pin "1") (pinfunction "1_1") (pintype "passive"))
      (node (ref "C32") (pin "2") (pinfunction "2_2") (pintype "passive"))
      (node (ref "C33") (pin "1") (pinfunction "1_1") (pintype "passive"))
      (node (ref "C34") (pin "1") (pinfunction "1_1") (pintype "passive"))
      (node (ref "C35") (pin "1") (pinfunction "1_1") (pintype "passive"))
      (node (ref "C36") (pin "1") (pinfunction "1_1") (pintype "passive"))
      (node (ref "C37") (pin "1") (pinfunction "1_1") (pintype "passive"))
      (node (ref "C38") (pin "1") (pinfunction "1_1") (pintype "passive"))
      (node (ref "C39") (pin "1") (pinfunction "1_1") (pintype "passive"))
      (node (ref "C4") (pin "1") (pinfunction "1_1") (pintype "passive"))
      (node (ref "C40") (pin "1") (pinfunction "1_1") (pintype "passive"))
      (node (ref "C41") (pin "1") (pinfunction "1_1") (pintype "passive"))
      (node (ref "C42") (pin "1") (pinfunction "1_1") (pintype "passive"))
      (node (ref "C5") (pin "2") (pinfunction "2_2") (pintype "passive"))
      (node (ref "C7") (pin "1") (pinfunction "1_1") (pintype "passive"))
      (node (ref "C9") (pin "2") (pinfunction "2_2") (pintype "passive"))
      (node (ref "DD1") (pin "11") (pinfunction "PC3_11") (pintype "passive"))
      (node (ref "DD1") (pin "12") (pinfunction "VSSA_12") (pintype "passive"))
      (node (ref "DD1") (pin "18") (pinfunction "VSS_4_18") (pintype "passive"))
      (node (ref "DD1") (pin "31") (pinfunction "VSS_1_31") (pintype "passive"))
      (node (ref "DD1") (pin "47") (pinfunction "VSS_2_47") (pintype "passive"))
      (node (ref "DD1") (pin "63") (pinfunction "VSS_3_63") (pintype "passive"))
      (node (ref "DD2") (pin "10") (pinfunction "AGND_10") (pintype "passive"))
      (node (ref "DD2") (pin "21") (pinfunction "GND_21") (pintype "passive"))
      (node (ref "DD2") (pin "31") (pinfunction "GND_31") (pintype "passive"))
      (node (ref "DD2") (pin "41") (pinfunction "GND_41") (pintype "passive"))
      (node (ref "G1") (pin "15") (pinfunction "PGND_15") (pintype "passive"))
      (node (ref "G1") (pin "16") (pinfunction "PGND_16") (pintype "passive"))
      (node (ref "L1") (pin "3") (pinfunction "3_3") (pintype "passive"))
      (node (ref "R1") (pin "2") (pinfunction "2_2") (pintype "passive"))
      (node (ref "R13") (pin "1") (pinfunction "1_1") (pintype "passive"))
      (node (ref "R2") (pin "1") (pinfunction "1_1") (pintype "passive"))
      (node (ref "R21") (pin "1") (pinfunction "1_1") (pintype "passive"))
      (node (ref "R26") (pin "1") (pinfunction "1_1") (pintype "passive"))
      (node (ref "R28") (pin "1") (pinfunction "1_1") (pintype "passive"))
      (node (ref "R4") (pin "2") (pinfunction "2_2") (pintype "passive"))
      (node (ref "R7") (pin "1") (pinfunction "1_1") (pintype "passive"))
      (node (ref "VD8") (pin "1") (pinfunction "1_1") (pintype "passive"))
      (node (ref "VT1") (pin "2") (pinfunction "2_2") (pintype "passive"))
      (node (ref "X3") (pin "6") (pinfunction "6_6") (pintype "passive"))
    )
    (net (code "19") (name "/LF Ethernet RX H") (class "Default")
      (node (ref "DD2") (pin "9") (pinfunction "RXP2_9") (pintype "passive"))
      (node (ref "R18") (pin "1") (pinfunction "1_1") (pintype "passive"))
      (node (ref "X2") (pin "9") (pinfunction "9_9") (pintype "passive"))
    )
    (net (code "20") (name "/LF Ethernet RX L") (class "Default")
      (node (ref "DD2") (pin "8") (pinfunction "RXM2_8") (pintype "passive"))
      (node (ref "R20") (pin "1") (pinfunction "1_1") (pintype "passive"))
      (node (ref "X2") (pin "10") (pinfunction "10_10") (pintype "passive"))
    )
    (net (code "21") (name "/LF Ethernet TX H") (class "Default")
      (node (ref "DD2") (pin "12") (pinfunction "TXP2_12") (pintype "passive"))
      (node (ref "R15") (pin "1") (pinfunction "1_1") (pintype "passive"))
      (node (ref "X2") (pin "1") (pinfunction "1_1") (pintype "passive"))
    )
    (net (code "22") (name "/LF Ethernet TX L") (class "Default")
      (node (ref "DD2") (pin "11") (pinfunction "TXM2_11") (pintype "passive"))
      (node (ref "R17") (pin "1") (pinfunction "1_1") (pintype "passive"))
      (node (ref "X2") (pin "2") (pinfunction "2_2") (pintype "passive"))
    )
    (net (code "23") (name "/LF_GND") (class "Default")
      (node (ref "K1") (pin "2") (pinfunction "2_2") (pintype "passive"))
      (node (ref "X2") (pin "7") (pinfunction "7_7") (pintype "passive"))
    )
    (net (code "24") (name "/LF_VCC") (class "Default")
      (node (ref "K1") (pin "7") (pinfunction "7_7") (pintype "passive"))
      (node (ref "X2") (pin "8") (pinfunction "8_8") (pintype "passive"))
    )
    (net (code "25") (name "/NIRQ") (class "Default")
      (node (ref "DD2") (pin "35") (pinfunction "INTRN_35") (pintype "passive"))
    )
    (net (code "26") (name "/NRST") (class "Default")
      (node (ref "C4") (pin "2") (pinfunction "2_2") (pintype "passive"))
      (node (ref "DD1") (pin "7") (pinfunction "NRST_7") (pintype "passive"))
      (node (ref "R5") (pin "1") (pinfunction "1_1") (pintype "passive"))
    )
    (net (code "27") (name "/OSC_IN") (class "Default")
      (node (ref "C2") (pin "2") (pinfunction "2_2") (pintype "passive"))
      (node (ref "DD1") (pin "5") (pinfunction "OSC_IN_5") (pintype "passive"))
      (node (ref "Q1") (pin "1") (pinfunction "1_1") (pintype "passive"))
    )
    (net (code "28") (name "/OSC_OUT") (class "Default")
      (node (ref "C3") (pin "2") (pinfunction "2_2") (pintype "passive"))
      (node (ref "DD1") (pin "6") (pinfunction "OSC_OUT_6") (pintype "passive"))
      (node (ref "Q1") (pin "2") (pinfunction "2_2") (pintype "passive"))
    )
    (net (code "29") (name "/PGOOD") (class "Default")
      (node (ref "G1") (pin "8") (pinfunction "PGOOD_8") (pintype "passive"))
    )
    (net (code "30") (name "/REL_2") (class "Default")
      (node (ref "DD1") (pin "10") (pinfunction "PC2_10") (pintype "passive"))
      (node (ref "R3") (pin "1") (pinfunction "1_1") (pintype "passive"))
    )
    (net (code "31") (name "/RMII_CLK") (class "Default")
      (node (ref "C18") (pin "1") (pinfunction "1_1") (pintype "passive"))
      (node (ref "DD1") (pin "15") (pinfunction "PA1/RMII_REF_CLK_15") (pintype "passive"))
    )
    (net (code "32") (name "/RMII_CRSDV") (class "Default")
      (node (ref "C21") (pin "1") (pinfunction "1_1") (pintype "passive"))
      (node (ref "DD1") (pin "23") (pinfunction "PA7/RMII_CRS_DV_23") (pintype "passive"))
    )
    (net (code "33") (name "/RMII_MDC") (class "Default")
      (node (ref "DD1") (pin "9") (pinfunction "PC1/RMII_MDC_9") (pintype "passive"))
      (node (ref "DD2") (pin "36") (pinfunction "SCL_MDC_36") (pintype "passive"))
      (node (ref "R24") (pin "2") (pinfunction "2_2") (pintype "passive"))
    )
    (net (code "34") (name "/RMII_MDIO") (class "Default")
      (node (ref "DD1") (pin "16") (pinfunction "PA2/RMII_MDIO_16") (pintype "passive"))
      (node (ref "DD2") (pin "37") (pinfunction "SDA_MDIO_37") (pintype "passive"))
      (node (ref "R25") (pin "2") (pinfunction "2_2") (pintype "passive"))
    )
    (net (code "35") (name "/RMII_RXD0") (class "Default")
      (node (ref "C23") (pin "1") (pinfunction "1_1") (pintype "passive"))
      (node (ref "DD1") (pin "24") (pinfunction "PC4/RMII_RXD0_24") (pintype "passive"))
    )
    (net (code "36") (name "/RMII_RXD1") (class "Default")
      (node (ref "C22") (pin "1") (pinfunction "1_1") (pintype "passive"))
      (node (ref "DD1") (pin "25") (pinfunction "PC5/RMII_RXD1_25") (pintype "passive"))
    )
    (net (code "37") (name "/RMII_TXD0") (class "Default")
      (node (ref "DD1") (pin "33") (pinfunction "PB12/RMII_TXD0_33") (pintype "passive"))
      (node (ref "DD2") (pin "20") (pinfunction "SMTXD30_20") (pintype "passive"))
    )
    (net (code "38") (name "/RMII_TXD1") (class "Default")
      (node (ref "DD1") (pin "34") (pinfunction "PB13/RMII_TXD1_34") (pintype "passive"))
      (node (ref "DD2") (pin "19") (pinfunction "SMTXD31_19") (pintype "passive"))
    )
    (net (code "39") (name "/RMII_TXEN") (class "Default")
      (node (ref "DD1") (pin "30") (pinfunction "PB11/RMII_TX_EN_30") (pintype "passive"))
      (node (ref "DD2") (pin "16") (pinfunction "SMTXEN3_16") (pintype "passive"))
    )
    (net (code "40") (name "/RS485RX+") (class "Default")
      (node (ref "AD1") (pin "9") (pinfunction "Y_9") (pintype "passive"))
      (node (ref "R19") (pin "1") (pinfunction "1_1") (pintype "passive"))
      (node (ref "RU5") (pin "2") (pinfunction "2_2") (pintype "passive"))
      (node (ref "SA1") (pin "2") (pinfunction "2_2") (pintype "passive"))
      (node (ref "VD9") (pin "1") (pinfunction "1_1") (pintype "passive"))
      (node (ref "X2") (pin "4") (pinfunction "4_4") (pintype "passive"))
    )
    (net (code "41") (name "/RS485RX-") (class "Default")
      (node (ref "AD1") (pin "10") (pinfunction "Z_10") (pintype "passive"))
      (node (ref "R16") (pin "1") (pinfunction "1_1") (pintype "passive"))
      (node (ref "RU6") (pin "2") (pinfunction "2_2") (pintype "passive"))
      (node (ref "SA1") (pin "1") (pinfunction "1_1") (pintype "passive"))
      (node (ref "VD9") (pin "2") (pinfunction "2_2") (pintype "passive"))
      (node (ref "X2") (pin "3") (pinfunction "3_3") (pintype "passive"))
    )
    (net (code "42") (name "/RS485TX+") (class "Default")
      (node (ref "AD1") (pin "12") (pinfunction "A_12") (pintype "passive"))
      (node (ref "R8") (pin "1") (pinfunction "1_1") (pintype "passive"))
      (node (ref "RU8") (pin "2") (pinfunction "2_2") (pintype "passive"))
      (node (ref "SA1") (pin "3") (pinfunction "3_3") (pintype "passive"))
      (node (ref "VD10") (pin "2") (pinfunction "2_2") (pintype "passive"))
      (node (ref "X2") (pin "6") (pinfunction "6_6") (pintype "passive"))
    )
    (net (code "43") (name "/RS485TX-") (class "Default")
      (node (ref "AD1") (pin "11") (pinfunction "B_11") (pintype "passive"))
      (node (ref "R11") (pin "1") (pinfunction "1_1") (pintype "passive"))
      (node (ref "RU7") (pin "2") (pinfunction "2_2") (pintype "passive"))
      (node (ref "SA1") (pin "4") (pinfunction "4_4") (pintype "passive"))
      (node (ref "VD10") (pin "1") (pinfunction "1_1") (pintype "passive"))
      (node (ref "X2") (pin "5") (pinfunction "5_5") (pintype "passive"))
    )
    (net (code "44") (name "/RSTN") (class "Default")
      (node (ref "C33") (pin "2") (pinfunction "2_2") (pintype "passive"))
      (node (ref "DD2") (pin "47") (pinfunction "RSTN_47") (pintype "passive"))
      (node (ref "R27") (pin "1") (pinfunction "1_1") (pintype "passive"))
      (node (ref "VD11") (pin "1") (pinfunction "1_1") (pintype "passive"))
    )
    (net (code "45") (name "/RX1+") (class "Default")
      (node (ref "DD2") (pin "2") (pinfunction "RXP1_2") (pintype "passive"))
      (node (ref "R12") (pin "2") (pinfunction "2_2") (pintype "passive"))
      (node (ref "T1") (pin "6") (pinfunction "6_6") (pintype "passive"))
    )
    (net (code "46") (name "/RX1-") (class "Default")
      (node (ref "DD2") (pin "1") (pinfunction "RXM1_1") (pintype "passive"))
      (node (ref "R14") (pin "2") (pinfunction "2_2") (pintype "passive"))
      (node (ref "T1") (pin "8") (pinfunction "8_8") (pintype "passive"))
    )
    (net (code "47") (name "/SPIQ") (class "Default")
      (node (ref "DD2") (pin "38") (pinfunction "SPIQ_38") (pintype "passive"))
      (node (ref "R22") (pin "2") (pinfunction "2_2") (pintype "passive"))
    )
    (net (code "48") (name "/SPISN") (class "Default")
      (node (ref "DD2") (pin "39") (pinfunction "SPISN_39") (pintype "passive"))
      (node (ref "R23") (pin "2") (pinfunction "2_2") (pintype "passive"))
    )
    (net (code "49") (name "/SWCLK") (class "Default")
      (node (ref "DD1") (pin "49") (pinfunction "PA14_49") (pintype "passive"))
      (node (ref "X3") (pin "3") (pinfunction "3_3") (pintype "passive"))
    )
    (net (code "50") (name "/SWDIO") (class "Default")
      (node (ref "DD1") (pin "46") (pinfunction "PA13_46") (pintype "passive"))
      (node (ref "X3") (pin "2") (pinfunction "2_2") (pintype "passive"))
    )
    (net (code "51") (name "/Sensor Ethernet RX H") (class "Default")
      (node (ref "FV2") (pin "1") (pinfunction "1_1") (pintype "passive"))
      (node (ref "T1") (pin "11") (pinfunction "11_11") (pintype "passive"))
      (node (ref "X1") (pin "9") (pinfunction "9_9") (pintype "passive"))
    )
    (net (code "52") (name "/Sensor Ethernet RX L") (class "Default")
      (node (ref "FV2") (pin "3") (pinfunction "3_3") (pintype "passive"))
      (node (ref "T1") (pin "9") (pinfunction "9_9") (pintype "passive"))
      (node (ref "X1") (pin "10") (pinfunction "10_10") (pintype "passive"))
    )
    (net (code "53") (name "/Sensor Ethernet TX H") (class "Default")
      (node (ref "FV1") (pin "1") (pinfunction "1_1") (pintype "passive"))
      (node (ref "T1") (pin "16") (pinfunction "16_16") (pintype "passive"))
      (node (ref "X1") (pin "1") (pinfunction "1_1") (pintype "passive"))
    )
    (net (code "54") (name "/Sensor Ethernet TX L") (class "Default")
      (node (ref "FV1") (pin "3") (pinfunction "3_3") (pintype "passive"))
      (node (ref "T1") (pin "14") (pinfunction "14_14") (pintype "passive"))
      (node (ref "X1") (pin "2") (pinfunction "2_2") (pintype "passive"))
    )
    (net (code "55") (name "/Sensor _GND") (class "Default")
      (node (ref "C6") (pin "1") (pinfunction "1_1") (pintype "passive"))
      (node (ref "FV4") (pin "3") (pinfunction "3_3") (pintype "passive"))
      (node (ref "K1") (pin "3") (pinfunction "3_3") (pintype "passive"))
      (node (ref "RU4") (pin "1") (pinfunction "1_1") (pintype "passive"))
      (node (ref "VD2") (pin "1") (pinfunction "1_1") (pintype "passive"))
      (node (ref "X1") (pin "7") (pinfunction "7_7") (pintype "passive"))
    )
    (net (code "56") (name "/Sensor_VCC") (class "Default")
      (node (ref "C6") (pin "2") (pinfunction "2_2") (pintype "passive"))
      (node (ref "FV4") (pin "1") (pinfunction "1_1") (pintype "passive"))
      (node (ref "K1") (pin "6") (pinfunction "6_6") (pintype "passive"))
      (node (ref "RU3") (pin "1") (pinfunction "1_1") (pintype "passive"))
      (node (ref "VD1") (pin "1") (pinfunction "1_1") (pintype "passive"))
      (node (ref "X1") (pin "8") (pinfunction "8_8") (pintype "passive"))
    )
    (net (code "57") (name "/TX1+") (class "Default")
      (node (ref "DD2") (pin "4") (pinfunction "TXP1_4") (pintype "passive"))
      (node (ref "R9") (pin "2") (pinfunction "2_2") (pintype "passive"))
      (node (ref "T1") (pin "1") (pinfunction "1_1") (pintype "passive"))
    )
    (net (code "58") (name "/TX1-") (class "Default")
      (node (ref "DD2") (pin "3") (pinfunction "TXM1_3") (pintype "passive"))
      (node (ref "R10") (pin "2") (pinfunction "2_2") (pintype "passive"))
      (node (ref "T1") (pin "3") (pinfunction "3_3") (pintype "passive"))
    )
    (net (code "59") (name "/UART_RX") (class "Default")
      (node (ref "AD1") (pin "2") (pinfunction "R_2") (pintype "passive"))
    )
    (net (code "60") (name "/UART_TX") (class "Default")
      (node (ref "AD1") (pin "5") (pinfunction "D_5") (pintype "passive"))
    )
    (net (code "61") (name "/USART1_RX") (class "Default")
      (node (ref "DD1") (pin "43") (pinfunction "PA10/USART1_RX_43") (pintype "passive"))
      (node (ref "X3") (pin "5") (pinfunction "5_5") (pintype "passive"))
    )
    (net (code "62") (name "/USART1_TX") (class "Default")
      (node (ref "DD1") (pin "42") (pinfunction "PA9/USART1_TX_42") (pintype "passive"))
      (node (ref "X3") (pin "4") (pinfunction "4_4") (pintype "passive"))
    )
    (net (code "63") (name "/VCC") (class "Default")
      (node (ref "C5") (pin "1") (pinfunction "1_1") (pintype "passive"))
      (node (ref "G1") (pin "12") (pinfunction "EN_12") (pintype "passive"))
      (node (ref "G1") (pin "13") (pinfunction "VIN_13") (pintype "passive"))
      (node (ref "G1") (pin "14") (pinfunction "VIN_14") (pintype "passive"))
      (node (ref "VD6") (pin "2") (pinfunction "2_2") (pintype "passive"))
      (node (ref "VD8") (pin "2") (pinfunction "2_2") (pintype "passive"))
    )
    (net (code "64") (name "Net-(C8-Pad2)") (class "Default")
      (node (ref "C8") (pin "2") (pinfunction "2_2") (pintype "passive"))
      (node (ref "G1") (pin "1") (pinfunction "SW_1") (pintype "passive"))
      (node (ref "G1") (pin "2") (pinfunction "SW_2") (pintype "passive"))
      (node (ref "L2") (pin "1") (pinfunction "1_1") (pintype "passive"))
    )
    (net (code "65") (name "Net-(C13-Pad2)") (class "Default")
      (node (ref "C13") (pin "2") (pinfunction "2_2") (pintype "passive"))
      (node (ref "R10") (pin "1") (pinfunction "1_1") (pintype "passive"))
      (node (ref "R9") (pin "1") (pinfunction "1_1") (pintype "passive"))
    )
    (net (code "66") (name "Net-(C14-Pad1)") (class "Default")
      (node (ref "C14") (pin "1") (pinfunction "1_1") (pintype "passive"))
      (node (ref "R11") (pin "2") (pinfunction "2_2") (pintype "passive"))
      (node (ref "R8") (pin "2") (pinfunction "2_2") (pintype "passive"))
    )
    (net (code "67") (name "Net-(C15-Pad2)") (class "Default")
      (node (ref "C15") (pin "2") (pinfunction "2_2") (pintype "passive"))
      (node (ref "R12") (pin "1") (pinfunction "1_1") (pintype "passive"))
      (node (ref "R14") (pin "1") (pinfunction "1_1") (pintype "passive"))
    )
    (net (code "68") (name "Net-(C16-Pad1)") (class "Default")
      (node (ref "C16") (pin "1") (pinfunction "1_1") (pintype "passive"))
      (node (ref "R15") (pin "2") (pinfunction "2_2") (pintype "passive"))
      (node (ref "R17") (pin "2") (pinfunction "2_2") (pintype "passive"))
    )
    (net (code "69") (name "Net-(C17-Pad1)") (class "Default")
      (node (ref "C17") (pin "1") (pinfunction "1_1") (pintype "passive"))
      (node (ref "R16") (pin "2") (pinfunction "2_2") (pintype "passive"))
      (node (ref "R19") (pin "2") (pinfunction "2_2") (pintype "passive"))
    )
    (net (code "70") (name "Net-(C20-Pad1)") (class "Default")
      (node (ref "C20") (pin "1") (pinfunction "1_1") (pintype "passive"))
      (node (ref "R18") (pin "2") (pinfunction "2_2") (pintype "passive"))
      (node (ref "R20") (pin "2") (pinfunction "2_2") (pintype "passive"))
    )
    (net (code "71") (name "Net-(C25-Pad2)") (class "Default")
      (node (ref "C25") (pin "2") (pinfunction "2_2") (pintype "passive"))
      (node (ref "T1") (pin "10") (pinfunction "10_10") (pintype "passive"))
      (node (ref "T1") (pin "15") (pinfunction "15_15") (pintype "passive"))
    )
    (net (code "72") (name "Net-(DA1-RS)") (class "Default")
      (node (ref "DA1") (pin "8") (pinfunction "RS_8") (pintype "passive"))
      (node (ref "R2") (pin "2") (pinfunction "2_2") (pintype "passive"))
    )
    (net (code "73") (name "Net-(DD1-BOOT0)") (class "Default")
      (node (ref "C7") (pin "2") (pinfunction "2_2") (pintype "passive"))
      (node (ref "DD1") (pin "60") (pinfunction "BOOT0_60") (pintype "passive"))
    )
    (net (code "74") (name "Net-(DD2-FXSD1)") (class "Default")
      (node (ref "DD2") (pin "48") (pinfunction "FXSD1_48") (pintype "passive"))
      (node (ref "R26") (pin "2") (pinfunction "2_2") (pintype "passive"))
    )
    (net (code "75") (name "Net-(DD2-ISET)") (class "Default")
      (node (ref "DD2") (pin "6") (pinfunction "ISET_6") (pintype "passive"))
      (node (ref "R28") (pin "2") (pinfunction "2_2") (pintype "passive"))
    )
    (net (code "76") (name "Net-(DD2-SMRXD30)") (class "Default")
      (node (ref "C23") (pin "2") (pinfunction "2_2") (pintype "passive"))
      (node (ref "DD2") (pin "29") (pinfunction "SMRXD30_29") (pintype "passive"))
      (node (ref "R21") (pin "2") (pinfunction "2_2") (pintype "passive"))
    )
    (net (code "77") (name "Net-(DD2-SMRXD31)") (class "Default")
      (node (ref "C22") (pin "2") (pinfunction "2_2") (pintype "passive"))
      (node (ref "DD2") (pin "28") (pinfunction "SMRXD31_28") (pintype "passive"))
    )
    (net (code "78") (name "Net-(DD2-SMRXD33)") (class "Default")
      (node (ref "C18") (pin "2") (pinfunction "2_2") (pintype "passive"))
      (node (ref "DD2") (pin "23") (pinfunction "SMTXC3_23") (pintype "passive"))
      (node (ref "DD2") (pin "26") (pinfunction "SMRXD33_26") (pintype "passive"))
      (node (ref "R13") (pin "2") (pinfunction "2_2") (pintype "passive"))
    )
    (net (code "79") (name "Net-(DD2-SMRXDV3)") (class "Default")
      (node (ref "C21") (pin "2") (pinfunction "2_2") (pintype "passive"))
      (node (ref "DD2") (pin "25") (pinfunction "SMRXDV3_25") (pintype "passive"))
    )
    (net (code "80") (name "Net-(DD2-X1)") (class "Default")
      (node (ref "C24") (pin "2") (pinfunction "2_2") (pintype "passive"))
      (node (ref "DD2") (pin "14") (pinfunction "X1_14") (pintype "passive"))
      (node (ref "Q2") (pin "2") (pinfunction "2_2") (pintype "passive"))
    )
    (net (code "81") (name "Net-(DD2-X2)") (class "Default")
      (node (ref "C26") (pin "2") (pinfunction "2_2") (pintype "passive"))
      (node (ref "DD2") (pin "15") (pinfunction "X2_15") (pintype "passive"))
      (node (ref "Q2") (pin "1") (pinfunction "1_1") (pintype "passive"))
    )
    (net (code "82") (name "Net-(G1-AGND)") (class "Default")
      (node (ref "C11") (pin "2") (pinfunction "2_2") (pintype "passive"))
      (node (ref "G1") (pin "10") (pinfunction "AGND_10") (pintype "passive"))
      (node (ref "G1") (pin "6") (pinfunction "SYNC_6") (pintype "passive"))
    )
    (net (code "83") (name "Net-(G1-CBOOT)") (class "Default")
      (node (ref "C8") (pin "1") (pinfunction "1_1") (pintype "passive"))
      (node (ref "G1") (pin "3") (pinfunction "CBOOT_3") (pintype "passive"))
    )
    (net (code "84") (name "Net-(G1-FB)") (class "Default")
      (node (ref "C10") (pin "1") (pinfunction "1_1") (pintype "passive"))
      (node (ref "G1") (pin "9") (pinfunction "FB_9") (pintype "passive"))
      (node (ref "R6") (pin "1") (pinfunction "1_1") (pintype "passive"))
      (node (ref "R7") (pin "2") (pinfunction "2_2") (pintype "passive"))
    )
    (net (code "85") (name "Net-(G1-SS{slash}TRK)") (class "Default")
      (node (ref "C11") (pin "1") (pinfunction "1_1") (pintype "passive"))
      (node (ref "G1") (pin "11") (pinfunction "SS/TRK_11") (pintype "passive"))
    )
    (net (code "86") (name "Net-(G1-VCC)") (class "Default")
      (node (ref "C12") (pin "2") (pinfunction "2_2") (pintype "passive"))
      (node (ref "G1") (pin "4") (pinfunction "VCC_4") (pintype "passive"))
    )
    (net (code "87") (name "Net-(K1-Pad8)") (class "Default")
      (node (ref "K1") (pin "8") (pinfunction "8_8") (pintype "passive"))
      (node (ref "VD4") (pin "1") (pinfunction "1_1") (pintype "passive"))
      (node (ref "VT1") (pin "3") (pinfunction "3_3") (pintype "passive"))
    )
    (net (code "88") (name "Net-(L1-Pad1)") (class "Default")
      (node (ref "L1") (pin "1") (pinfunction "1_1") (pintype "passive"))
      (node (ref "RU3") (pin "2") (pinfunction "2_2") (pintype "passive"))
    )
    (net (code "89") (name "Net-(L1-Pad2)") (class "Default")
      (node (ref "L1") (pin "2") (pinfunction "2_2") (pintype "passive"))
      (node (ref "VD6") (pin "1") (pinfunction "1_1") (pintype "passive"))
    )
    (net (code "90") (name "Net-(L1-Pad4)") (class "Default")
      (node (ref "L1") (pin "4") (pinfunction "4_4") (pintype "passive"))
      (node (ref "RU4") (pin "2") (pinfunction "2_2") (pintype "passive"))
    )
    (net (code "91") (name "Net-(R3-Pad2)") (class "Default")
      (node (ref "R3") (pin "2") (pinfunction "2_2") (pintype "passive"))
      (node (ref "R4") (pin "1") (pinfunction "1_1") (pintype "passive"))
      (node (ref "VT1") (pin "1") (pinfunction "1_1") (pintype "passive"))
    )
    (net (code "92") (name "unconnected-(AD1-NC-Pad1)") (class "Default")
      (node (ref "AD1") (pin "1") (pinfunction "NC_1") (pintype "passive"))
    )
    (net (code "93") (name "unconnected-(AD1-NC-Pad8)") (class "Default")
      (node (ref "AD1") (pin "8") (pinfunction "NC_8") (pintype "passive"))
    )
    (net (code "94") (name "unconnected-(AD1-NC-Pad13)") (class "Default")
      (node (ref "AD1") (pin "13") (pinfunction "NC_13") (pintype "passive"))
    )
    (net (code "95") (name "unconnected-(DA1-VDD-Pad3)") (class "Default")
      (node (ref "DA1") (pin "3") (pinfunction "VDD_3") (pintype "passive"))
    )
    (net (code "96") (name "unconnected-(DA1-VREF-Pad5)") (class "Default")
      (node (ref "DA1") (pin "5") (pinfunction "VREF_5") (pintype "passive"))
    )
    (net (code "97") (name "unconnected-(DA1-VSS-Pad2)") (class "Default")
      (node (ref "DA1") (pin "2") (pinfunction "VSS_2") (pintype "passive"))
    )
    (net (code "98") (name "unconnected-(DD1-BOOT1-Pad28)") (class "Default")
      (node (ref "DD1") (pin "28") (pinfunction "BOOT1_28") (pintype "passive"))
    )
    (net (code "99") (name "unconnected-(DD1-PA0-Pad14)") (class "Default")
      (node (ref "DD1") (pin "14") (pinfunction "PA0_14") (pintype "passive"))
    )
    (net (code "100") (name "unconnected-(DD1-PA3{slash}USART2_RX-Pad17)") (class "Default")
      (node (ref "DD1") (pin "17") (pinfunction "PA3/USART2_RX_17") (pintype "passive"))
    )
    (net (code "101") (name "unconnected-(DD1-PA4-Pad20)") (class "Default")
      (node (ref "DD1") (pin "20") (pinfunction "PA4_20") (pintype "passive"))
    )
    (net (code "102") (name "unconnected-(DD1-PA5-Pad21)") (class "Default")
      (node (ref "DD1") (pin "21") (pinfunction "PA5_21") (pintype "passive"))
    )
    (net (code "103") (name "unconnected-(DD1-PA6-Pad22)") (class "Default")
      (node (ref "DD1") (pin "22") (pinfunction "PA6_22") (pintype "passive"))
    )
    (net (code "104") (name "unconnected-(DD1-PA8-Pad41)") (class "Default")
      (node (ref "DD1") (pin "41") (pinfunction "PA8_41") (pintype "passive"))
    )
    (net (code "105") (name "unconnected-(DD1-PA15-Pad50)") (class "Default")
      (node (ref "DD1") (pin "50") (pinfunction "PA15_50") (pintype "passive"))
    )
    (net (code "106") (name "unconnected-(DD1-PB0-Pad26)") (class "Default")
      (node (ref "DD1") (pin "26") (pinfunction "PB0_26") (pintype "passive"))
    )
    (net (code "107") (name "unconnected-(DD1-PB1-Pad27)") (class "Default")
      (node (ref "DD1") (pin "27") (pinfunction "PB1_27") (pintype "passive"))
    )
    (net (code "108") (name "unconnected-(DD1-PB3-Pad55)") (class "Default")
      (node (ref "DD1") (pin "55") (pinfunction "PB3_55") (pintype "passive"))
    )
    (net (code "109") (name "unconnected-(DD1-PB4-Pad56)") (class "Default")
      (node (ref "DD1") (pin "56") (pinfunction "PB4_56") (pintype "passive"))
    )
    (net (code "110") (name "unconnected-(DD1-PB5-Pad57)") (class "Default")
      (node (ref "DD1") (pin "57") (pinfunction "PB5_57") (pintype "passive"))
    )
    (net (code "111") (name "unconnected-(DD1-PB6-Pad58)") (class "Default")
      (node (ref "DD1") (pin "58") (pinfunction "PB6_58") (pintype "passive"))
    )
    (net (code "112") (name "unconnected-(DD1-PB7-Pad59)") (class "Default")
      (node (ref "DD1") (pin "59") (pinfunction "PB7_59") (pintype "passive"))
    )
    (net (code "113") (name "unconnected-(DD1-PB8-Pad61)") (class "Default")
      (node (ref "DD1") (pin "61") (pinfunction "PB8_61") (pintype "passive"))
    )
    (net (code "114") (name "unconnected-(DD1-PB9-Pad62)") (class "Default")
      (node (ref "DD1") (pin "62") (pinfunction "PB9_62") (pintype "passive"))
    )
    (net (code "115") (name "unconnected-(DD1-PB10{slash}USART3_TX-Pad29)") (class "Default")
      (node (ref "DD1") (pin "29") (pinfunction "PB10/USART3_TX_29") (pintype "passive"))
    )
    (net (code "116") (name "unconnected-(DD1-PB14-Pad35)") (class "Default")
      (node (ref "DD1") (pin "35") (pinfunction "PB14_35") (pintype "passive"))
    )
    (net (code "117") (name "unconnected-(DD1-PB15-Pad36)") (class "Default")
      (node (ref "DD1") (pin "36") (pinfunction "PB15_36") (pintype "passive"))
    )
    (net (code "118") (name "unconnected-(DD1-PC0-Pad8)") (class "Default")
      (node (ref "DD1") (pin "8") (pinfunction "PC0_8") (pintype "passive"))
    )
    (net (code "119") (name "unconnected-(DD1-PC6-Pad37)") (class "Default")
      (node (ref "DD1") (pin "37") (pinfunction "PC6_37") (pintype "passive"))
    )
    (net (code "120") (name "unconnected-(DD1-PC7-Pad38)") (class "Default")
      (node (ref "DD1") (pin "38") (pinfunction "PC7_38") (pintype "passive"))
    )
    (net (code "121") (name "unconnected-(DD1-PC8-Pad39)") (class "Default")
      (node (ref "DD1") (pin "39") (pinfunction "PC8_39") (pintype "passive"))
    )
    (net (code "122") (name "unconnected-(DD1-PC9-Pad40)") (class "Default")
      (node (ref "DD1") (pin "40") (pinfunction "PC9_40") (pintype "passive"))
    )
    (net (code "123") (name "unconnected-(DD1-PC10{slash}UART4_TX-Pad51)") (class "Default")
      (node (ref "DD1") (pin "51") (pinfunction "PC10/UART4_TX_51") (pintype "passive"))
    )
    (net (code "124") (name "unconnected-(DD1-PC11{slash}UART4_RX-Pad52)") (class "Default")
      (node (ref "DD1") (pin "52") (pinfunction "PC11/UART4_RX_52") (pintype "passive"))
    )
    (net (code "125") (name "unconnected-(DD1-PC12{slash}UART5_TX-Pad53)") (class "Default")
      (node (ref "DD1") (pin "53") (pinfunction "PC12/UART5_TX_53") (pintype "passive"))
    )
    (net (code "126") (name "unconnected-(DD1-PC13-Pad2)") (class "Default")
      (node (ref "DD1") (pin "2") (pinfunction "PC13_2") (pintype "passive"))
    )
    (net (code "127") (name "unconnected-(DD1-PC14-Pad3)") (class "Default")
      (node (ref "DD1") (pin "3") (pinfunction "PC14_3") (pintype "passive"))
    )
    (net (code "128") (name "unconnected-(DD1-PC15-Pad4)") (class "Default")
      (node (ref "DD1") (pin "4") (pinfunction "PC15_4") (pintype "passive"))
    )
    (net (code "129") (name "unconnected-(DD1-PD2{slash}UART5_RX-Pad54)") (class "Default")
      (node (ref "DD1") (pin "54") (pinfunction "PD2/UART5_RX_54") (pintype "passive"))
    )
    (net (code "130") (name "unconnected-(DD2-FXSD2-Pad13)") (class "Default")
      (node (ref "DD2") (pin "13") (pinfunction "FXSD2_13") (pintype "passive"))
    )
    (net (code "131") (name "unconnected-(DD2-P1LED0-Pad44)") (class "Default")
      (node (ref "DD2") (pin "44") (pinfunction "P1LED0_44") (pintype "passive"))
    )
    (net (code "132") (name "unconnected-(DD2-P1LED1-Pad43)") (class "Default")
      (node (ref "DD2") (pin "43") (pinfunction "P1LED1_43") (pintype "passive"))
    )
    (net (code "133") (name "unconnected-(DD2-P2LED0-Pad46)") (class "Default")
      (node (ref "DD2") (pin "46") (pinfunction "P2LED0_46") (pintype "passive"))
    )
    (net (code "134") (name "unconnected-(DD2-P2LED1-Pad45)") (class "Default")
      (node (ref "DD2") (pin "45") (pinfunction "P2LED1_45") (pintype "passive"))
    )
    (net (code "135") (name "unconnected-(DD2-SCOL3-Pad33)") (class "Default")
      (node (ref "DD2") (pin "33") (pinfunction "SCOL3_33") (pintype "passive"))
    )
    (net (code "136") (name "unconnected-(DD2-SCRS3-Pad34)") (class "Default")
      (node (ref "DD2") (pin "34") (pinfunction "SCRS3_34") (pintype "passive"))
    )
    (net (code "137") (name "unconnected-(DD2-SMRXC3-Pad30)") (class "Default")
      (node (ref "DD2") (pin "30") (pinfunction "SMRXC3_30") (pintype "passive"))
    )
    (net (code "138") (name "unconnected-(DD2-SMRXD32-Pad27)") (class "Default")
      (node (ref "DD2") (pin "27") (pinfunction "SMRXD32_27") (pintype "passive"))
    )
    (net (code "139") (name "unconnected-(DD2-SMTXD32-Pad18)") (class "Default")
      (node (ref "DD2") (pin "18") (pinfunction "SMTXD32_18") (pintype "passive"))
    )
    (net (code "140") (name "unconnected-(DD2-SMTXD33-Pad17)") (class "Default")
      (node (ref "DD2") (pin "17") (pinfunction "SMTXD33_17") (pintype "passive"))
    )
    (net (code "141") (name "unconnected-(DD2-SMTXER3-Pad24)") (class "Default")
      (node (ref "DD2") (pin "24") (pinfunction "SMTXER3_24") (pintype "passive"))
    )
    (net (code "142") (name "unconnected-(G1-RT-Pad7)") (class "Default")
      (node (ref "G1") (pin "7") (pinfunction "RT_7") (pintype "passive"))
    )
    (net (code "143") (name "unconnected-(K1-Pad4)") (class "Default")
      (node (ref "K1") (pin "4") (pinfunction "4_4") (pintype "passive"))
    )
    (net (code "144") (name "unconnected-(K1-Pad5)") (class "Default")
      (node (ref "K1") (pin "5") (pinfunction "5_5") (pintype "passive"))
    )
  )
)
